# VMEConnectors.net
KiCad netlist of a schematic drawn in Altium Designer
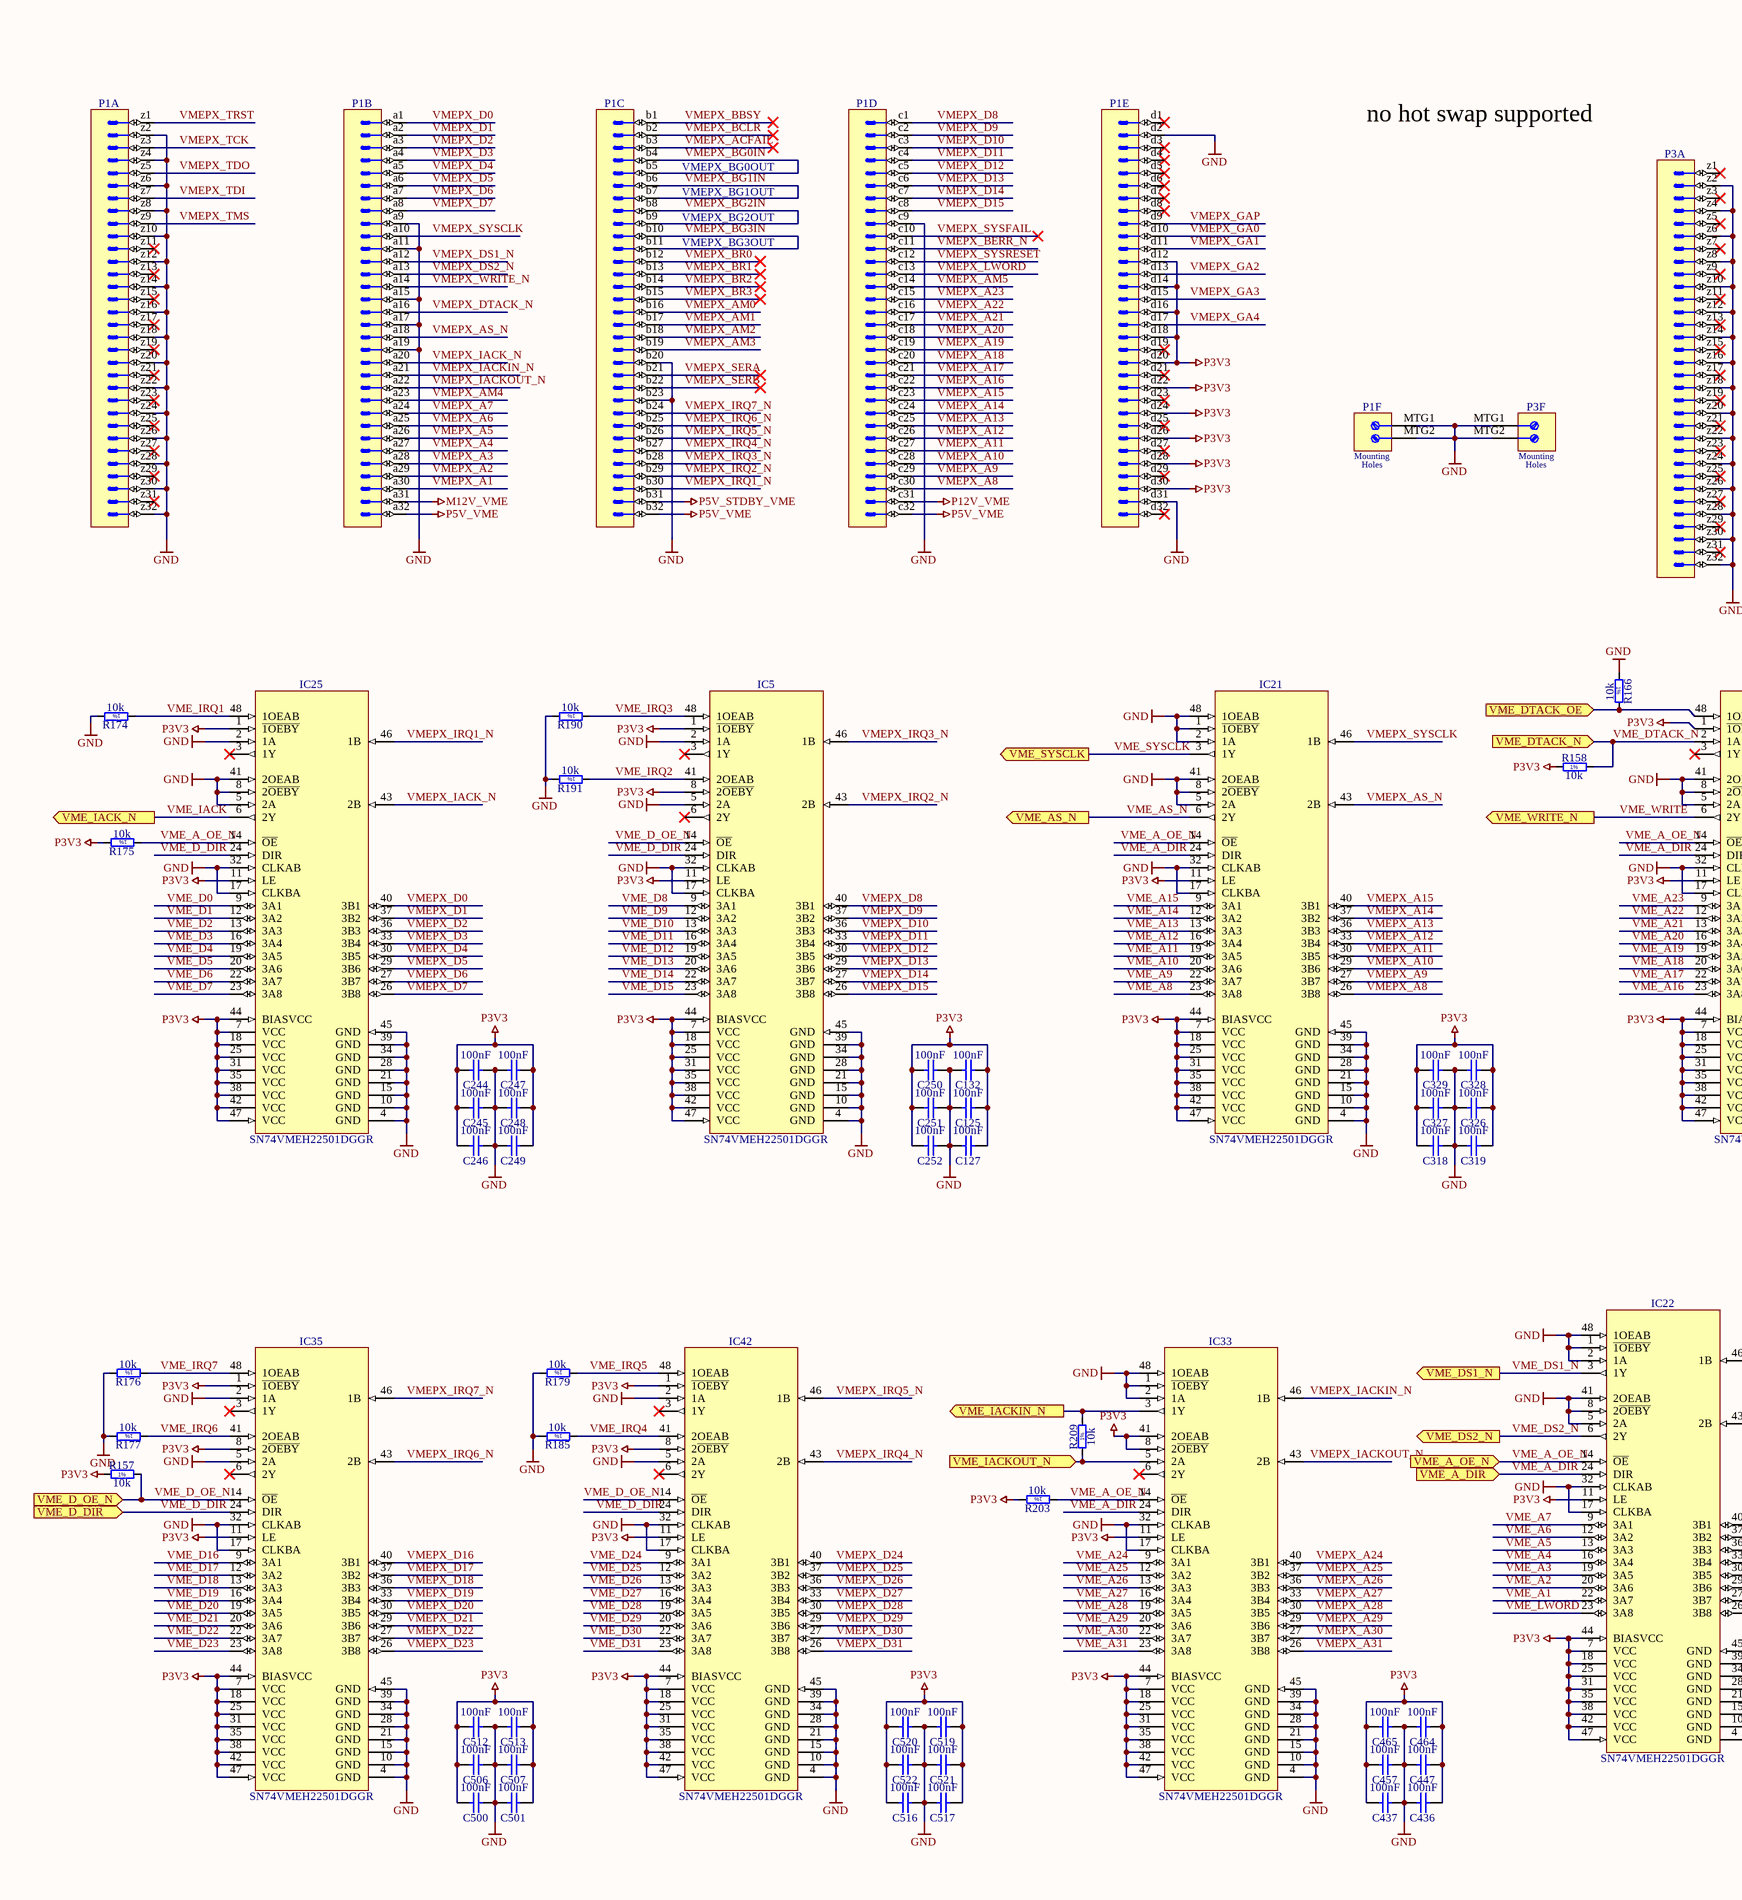
[diagram p0: VMEConnectors.SchDoc, left]
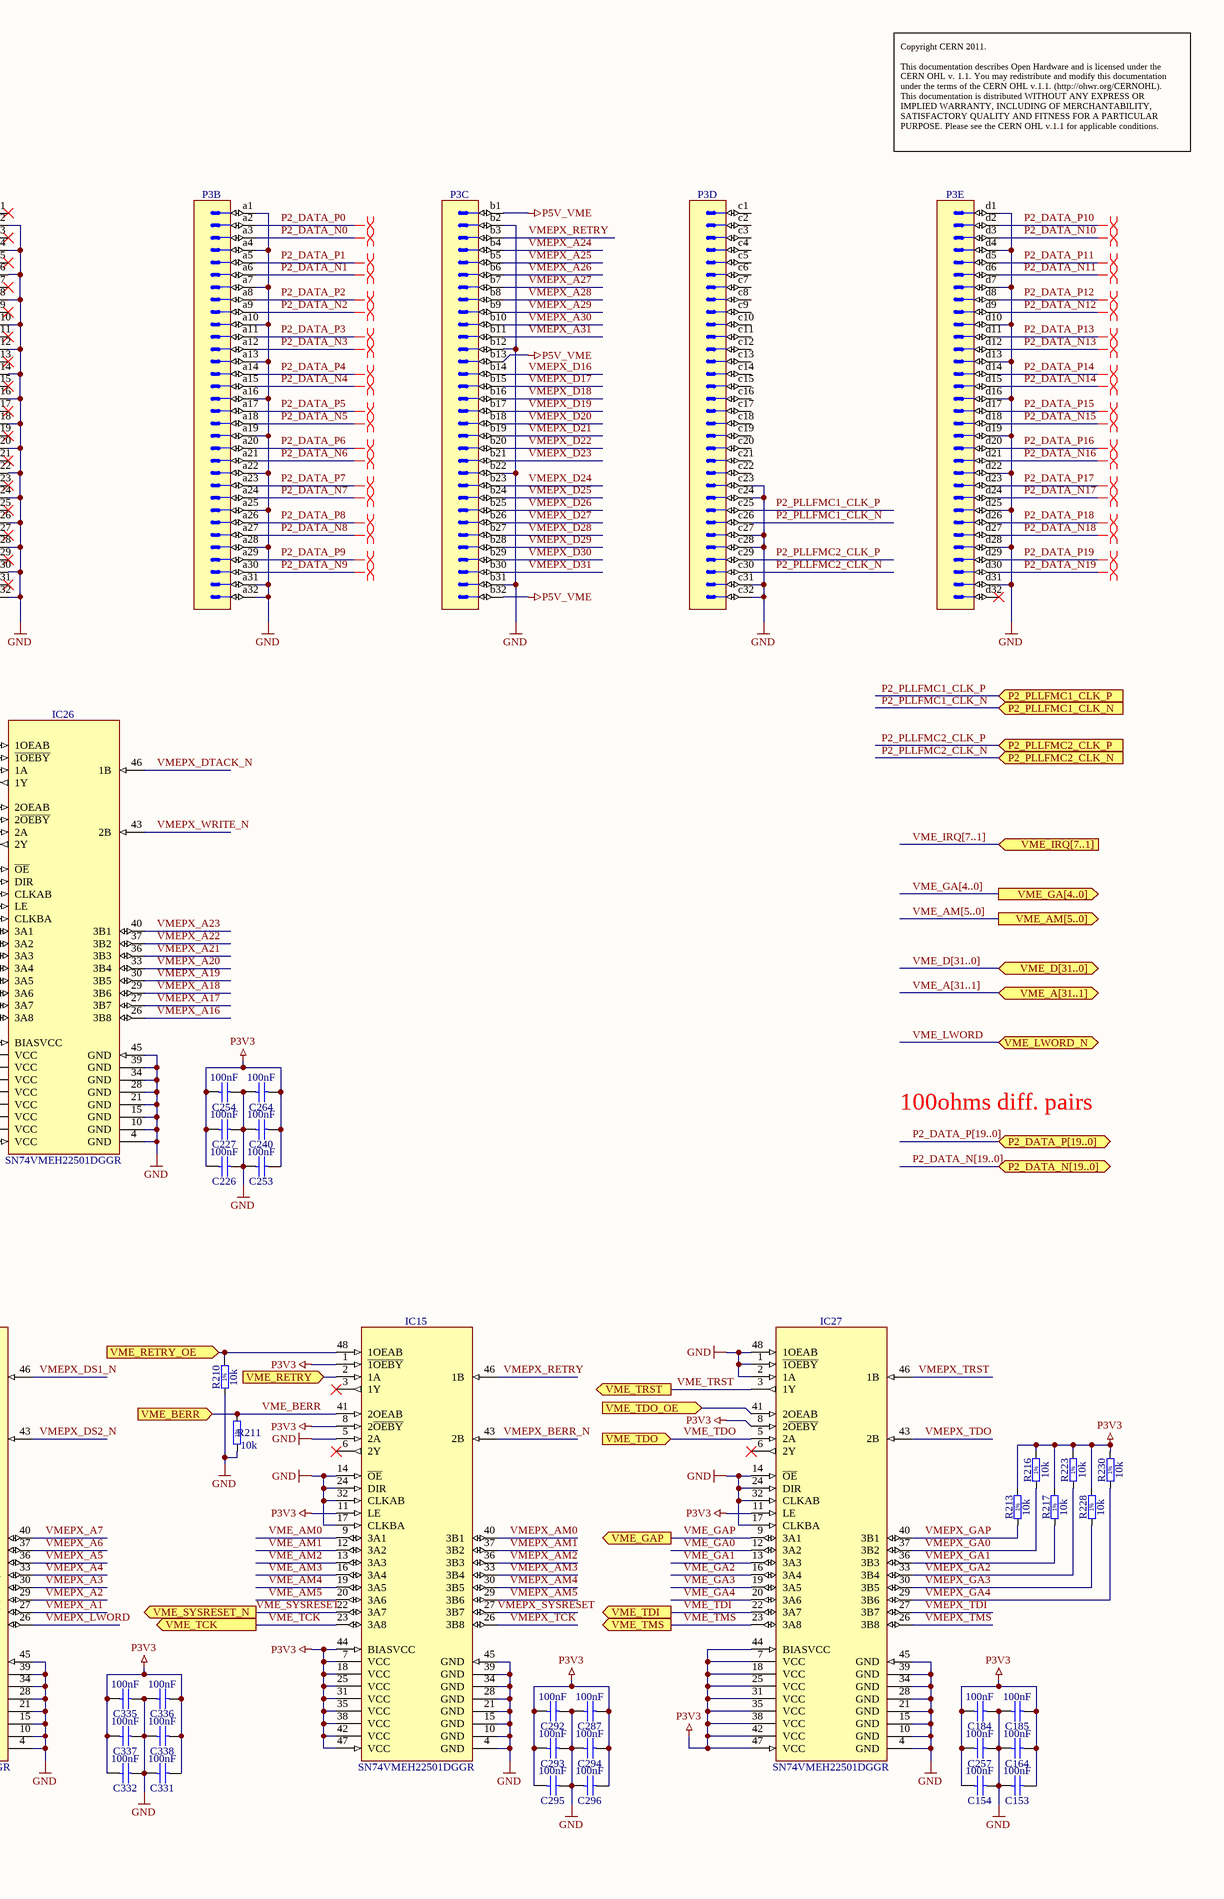
[diagram p1: VMEConnectors.SchDoc, right]

(export (version "E")
  (design (tool "Eeschema 10.0.6"))
  (components
    (comp (ref "C125")
      (value "100nF")
      (footprint "CAPC1005X55N")
      (description "Non-polarised capacitor")
      (fields
        (field (name "PART NUMBER") "CC0402_100NF_16V_10%_X7R")
        (field (name "VOLTAGE") "16V")
        (field (name "AUTHOR") "CERN DEM JLC")
      )
      (libsource (lib "Capacitors") (part "Capacitor - non polarized"))
    )
    (comp (ref "C127")
      (value "100nF")
      (footprint "CAPC1005X55N")
      (description "Non-polarised capacitor")
      (fields
        (field (name "PART NUMBER") "CC0402_100NF_16V_10%_X7R")
        (field (name "VOLTAGE") "16V")
        (field (name "AUTHOR") "CERN DEM JLC")
      )
      (libsource (lib "Capacitors") (part "Capacitor - non polarized"))
    )
    (comp (ref "C132")
      (value "100nF")
      (footprint "CAPC1005X55N")
      (description "Non-polarised capacitor")
      (fields
        (field (name "PART NUMBER") "CC0402_100NF_16V_10%_X7R")
        (field (name "VOLTAGE") "16V")
        (field (name "AUTHOR") "CERN DEM JLC")
      )
      (libsource (lib "Capacitors") (part "Capacitor - non polarized"))
    )
    (comp (ref "C153")
      (value "100nF")
      (footprint "CAPC1005X55N")
      (description "Non-polarised capacitor")
      (fields
        (field (name "PART NUMBER") "CC0402_100NF_16V_10%_X7R")
        (field (name "VOLTAGE") "16V")
        (field (name "AUTHOR") "CERN DEM JLC")
      )
      (libsource (lib "Capacitors") (part "Capacitor - non polarized"))
    )
    (comp (ref "C154")
      (value "100nF")
      (footprint "CAPC1005X55N")
      (description "Non-polarised capacitor")
      (fields
        (field (name "PART NUMBER") "CC0402_100NF_16V_10%_X7R")
        (field (name "VOLTAGE") "16V")
        (field (name "AUTHOR") "CERN DEM JLC")
      )
      (libsource (lib "Capacitors") (part "Capacitor - non polarized"))
    )
    (comp (ref "C164")
      (value "100nF")
      (footprint "CAPC1005X55N")
      (description "Non-polarised capacitor")
      (fields
        (field (name "PART NUMBER") "CC0402_100NF_16V_10%_X7R")
        (field (name "VOLTAGE") "16V")
        (field (name "AUTHOR") "CERN DEM JLC")
      )
      (libsource (lib "Capacitors") (part "Capacitor - non polarized"))
    )
    (comp (ref "C184")
      (value "100nF")
      (footprint "CAPC1005X55N")
      (description "Non-polarised capacitor")
      (fields
        (field (name "PART NUMBER") "CC0402_100NF_16V_10%_X7R")
        (field (name "VOLTAGE") "16V")
        (field (name "AUTHOR") "CERN DEM JLC")
      )
      (libsource (lib "Capacitors") (part "Capacitor - non polarized"))
    )
    (comp (ref "C185")
      (value "100nF")
      (footprint "CAPC1005X55N")
      (description "Non-polarised capacitor")
      (fields
        (field (name "PART NUMBER") "CC0402_100NF_16V_10%_X7R")
        (field (name "VOLTAGE") "16V")
        (field (name "AUTHOR") "CERN DEM JLC")
      )
      (libsource (lib "Capacitors") (part "Capacitor - non polarized"))
    )
    (comp (ref "C226")
      (value "100nF")
      (footprint "CAPC1005X55N")
      (description "Non-polarised capacitor")
      (fields
        (field (name "PART NUMBER") "CC0402_100NF_16V_10%_X7R")
        (field (name "VOLTAGE") "16V")
        (field (name "AUTHOR") "CERN DEM JLC")
      )
      (libsource (lib "Capacitors") (part "Capacitor - non polarized"))
    )
    (comp (ref "C227")
      (value "100nF")
      (footprint "CAPC1005X55N")
      (description "Non-polarised capacitor")
      (fields
        (field (name "PART NUMBER") "CC0402_100NF_16V_10%_X7R")
        (field (name "VOLTAGE") "16V")
        (field (name "AUTHOR") "CERN DEM JLC")
      )
      (libsource (lib "Capacitors") (part "Capacitor - non polarized"))
    )
    (comp (ref "C240")
      (value "100nF")
      (footprint "CAPC1005X55N")
      (description "Non-polarised capacitor")
      (fields
        (field (name "PART NUMBER") "CC0402_100NF_16V_10%_X7R")
        (field (name "VOLTAGE") "16V")
        (field (name "AUTHOR") "CERN DEM JLC")
      )
      (libsource (lib "Capacitors") (part "Capacitor - non polarized"))
    )
    (comp (ref "C244")
      (value "100nF")
      (footprint "CAPC1005X55N")
      (description "Non-polarised capacitor")
      (fields
        (field (name "PART NUMBER") "CC0402_100NF_16V_10%_X7R")
        (field (name "VOLTAGE") "16V")
        (field (name "AUTHOR") "CERN DEM JLC")
      )
      (libsource (lib "Capacitors") (part "Capacitor - non polarized"))
    )
    (comp (ref "C245")
      (value "100nF")
      (footprint "CAPC1005X55N")
      (description "Non-polarised capacitor")
      (fields
        (field (name "PART NUMBER") "CC0402_100NF_16V_10%_X7R")
        (field (name "VOLTAGE") "16V")
        (field (name "AUTHOR") "CERN DEM JLC")
      )
      (libsource (lib "Capacitors") (part "Capacitor - non polarized"))
    )
    (comp (ref "C246")
      (value "100nF")
      (footprint "CAPC1005X55N")
      (description "Non-polarised capacitor")
      (fields
        (field (name "PART NUMBER") "CC0402_100NF_16V_10%_X7R")
        (field (name "VOLTAGE") "16V")
        (field (name "AUTHOR") "CERN DEM JLC")
      )
      (libsource (lib "Capacitors") (part "Capacitor - non polarized"))
    )
    (comp (ref "C247")
      (value "100nF")
      (footprint "CAPC1005X55N")
      (description "Non-polarised capacitor")
      (fields
        (field (name "PART NUMBER") "CC0402_100NF_16V_10%_X7R")
        (field (name "VOLTAGE") "16V")
        (field (name "AUTHOR") "CERN DEM JLC")
      )
      (libsource (lib "Capacitors") (part "Capacitor - non polarized"))
    )
    (comp (ref "C248")
      (value "100nF")
      (footprint "CAPC1005X55N")
      (description "Non-polarised capacitor")
      (fields
        (field (name "PART NUMBER") "CC0402_100NF_16V_10%_X7R")
        (field (name "VOLTAGE") "16V")
        (field (name "AUTHOR") "CERN DEM JLC")
      )
      (libsource (lib "Capacitors") (part "Capacitor - non polarized"))
    )
    (comp (ref "C249")
      (value "100nF")
      (footprint "CAPC1005X55N")
      (description "Non-polarised capacitor")
      (fields
        (field (name "PART NUMBER") "CC0402_100NF_16V_10%_X7R")
        (field (name "VOLTAGE") "16V")
        (field (name "AUTHOR") "CERN DEM JLC")
      )
      (libsource (lib "Capacitors") (part "Capacitor - non polarized"))
    )
    (comp (ref "C250")
      (value "100nF")
      (footprint "CAPC1005X55N")
      (description "Non-polarised capacitor")
      (fields
        (field (name "PART NUMBER") "CC0402_100NF_16V_10%_X7R")
        (field (name "VOLTAGE") "16V")
        (field (name "AUTHOR") "CERN DEM JLC")
      )
      (libsource (lib "Capacitors") (part "Capacitor - non polarized"))
    )
    (comp (ref "C251")
      (value "100nF")
      (footprint "CAPC1005X55N")
      (description "Non-polarised capacitor")
      (fields
        (field (name "PART NUMBER") "CC0402_100NF_16V_10%_X7R")
        (field (name "VOLTAGE") "16V")
        (field (name "AUTHOR") "CERN DEM JLC")
      )
      (libsource (lib "Capacitors") (part "Capacitor - non polarized"))
    )
    (comp (ref "C252")
      (value "100nF")
      (footprint "CAPC1005X55N")
      (description "Non-polarised capacitor")
      (fields
        (field (name "PART NUMBER") "CC0402_100NF_16V_10%_X7R")
        (field (name "VOLTAGE") "16V")
        (field (name "AUTHOR") "CERN DEM JLC")
      )
      (libsource (lib "Capacitors") (part "Capacitor - non polarized"))
    )
    (comp (ref "C253")
      (value "100nF")
      (footprint "CAPC1005X55N")
      (description "Non-polarised capacitor")
      (fields
        (field (name "PART NUMBER") "CC0402_100NF_16V_10%_X7R")
        (field (name "VOLTAGE") "16V")
        (field (name "AUTHOR") "CERN DEM JLC")
      )
      (libsource (lib "Capacitors") (part "Capacitor - non polarized"))
    )
    (comp (ref "C254")
      (value "100nF")
      (footprint "CAPC1005X55N")
      (description "Non-polarised capacitor")
      (fields
        (field (name "PART NUMBER") "CC0402_100NF_16V_10%_X7R")
        (field (name "VOLTAGE") "16V")
        (field (name "AUTHOR") "CERN DEM JLC")
      )
      (libsource (lib "Capacitors") (part "Capacitor - non polarized"))
    )
    (comp (ref "C257")
      (value "100nF")
      (footprint "CAPC1005X55N")
      (description "Non-polarised capacitor")
      (fields
        (field (name "PART NUMBER") "CC0402_100NF_16V_10%_X7R")
        (field (name "VOLTAGE") "16V")
        (field (name "AUTHOR") "CERN DEM JLC")
      )
      (libsource (lib "Capacitors") (part "Capacitor - non polarized"))
    )
    (comp (ref "C264")
      (value "100nF")
      (footprint "CAPC1005X55N")
      (description "Non-polarised capacitor")
      (fields
        (field (name "PART NUMBER") "CC0402_100NF_16V_10%_X7R")
        (field (name "VOLTAGE") "16V")
        (field (name "AUTHOR") "CERN DEM JLC")
      )
      (libsource (lib "Capacitors") (part "Capacitor - non polarized"))
    )
    (comp (ref "C287")
      (value "100nF")
      (footprint "CAPC1005X55N")
      (description "Non-polarised capacitor")
      (fields
        (field (name "PART NUMBER") "CC0402_100NF_16V_10%_X7R")
        (field (name "VOLTAGE") "16V")
        (field (name "AUTHOR") "CERN DEM JLC")
      )
      (libsource (lib "Capacitors") (part "Capacitor - non polarized"))
    )
    (comp (ref "C292")
      (value "100nF")
      (footprint "CAPC1005X55N")
      (description "Non-polarised capacitor")
      (fields
        (field (name "PART NUMBER") "CC0402_100NF_16V_10%_X7R")
        (field (name "VOLTAGE") "16V")
        (field (name "AUTHOR") "CERN DEM JLC")
      )
      (libsource (lib "Capacitors") (part "Capacitor - non polarized"))
    )
    (comp (ref "C293")
      (value "100nF")
      (footprint "CAPC1005X55N")
      (description "Non-polarised capacitor")
      (fields
        (field (name "PART NUMBER") "CC0402_100NF_16V_10%_X7R")
        (field (name "VOLTAGE") "16V")
        (field (name "AUTHOR") "CERN DEM JLC")
      )
      (libsource (lib "Capacitors") (part "Capacitor - non polarized"))
    )
    (comp (ref "C294")
      (value "100nF")
      (footprint "CAPC1005X55N")
      (description "Non-polarised capacitor")
      (fields
        (field (name "PART NUMBER") "CC0402_100NF_16V_10%_X7R")
        (field (name "VOLTAGE") "16V")
        (field (name "AUTHOR") "CERN DEM JLC")
      )
      (libsource (lib "Capacitors") (part "Capacitor - non polarized"))
    )
    (comp (ref "C295")
      (value "100nF")
      (footprint "CAPC1005X55N")
      (description "Non-polarised capacitor")
      (fields
        (field (name "PART NUMBER") "CC0402_100NF_16V_10%_X7R")
        (field (name "VOLTAGE") "16V")
        (field (name "AUTHOR") "CERN DEM JLC")
      )
      (libsource (lib "Capacitors") (part "Capacitor - non polarized"))
    )
    (comp (ref "C296")
      (value "100nF")
      (footprint "CAPC1005X55N")
      (description "Non-polarised capacitor")
      (fields
        (field (name "PART NUMBER") "CC0402_100NF_16V_10%_X7R")
        (field (name "VOLTAGE") "16V")
        (field (name "AUTHOR") "CERN DEM JLC")
      )
      (libsource (lib "Capacitors") (part "Capacitor - non polarized"))
    )
    (comp (ref "C318")
      (value "100nF")
      (footprint "CAPC1005X55N")
      (description "Non-polarised capacitor")
      (fields
        (field (name "PART NUMBER") "CC0402_100NF_16V_10%_X7R")
        (field (name "VOLTAGE") "16V")
        (field (name "AUTHOR") "CERN DEM JLC")
      )
      (libsource (lib "Capacitors") (part "Capacitor - non polarized"))
    )
    (comp (ref "C319")
      (value "100nF")
      (footprint "CAPC1005X55N")
      (description "Non-polarised capacitor")
      (fields
        (field (name "PART NUMBER") "CC0402_100NF_16V_10%_X7R")
        (field (name "VOLTAGE") "16V")
        (field (name "AUTHOR") "CERN DEM JLC")
      )
      (libsource (lib "Capacitors") (part "Capacitor - non polarized"))
    )
    (comp (ref "C326")
      (value "100nF")
      (footprint "CAPC1005X55N")
      (description "Non-polarised capacitor")
      (fields
        (field (name "PART NUMBER") "CC0402_100NF_16V_10%_X7R")
        (field (name "VOLTAGE") "16V")
        (field (name "AUTHOR") "CERN DEM JLC")
      )
      (libsource (lib "Capacitors") (part "Capacitor - non polarized"))
    )
    (comp (ref "C327")
      (value "100nF")
      (footprint "CAPC1005X55N")
      (description "Non-polarised capacitor")
      (fields
        (field (name "PART NUMBER") "CC0402_100NF_16V_10%_X7R")
        (field (name "VOLTAGE") "16V")
        (field (name "AUTHOR") "CERN DEM JLC")
      )
      (libsource (lib "Capacitors") (part "Capacitor - non polarized"))
    )
    (comp (ref "C328")
      (value "100nF")
      (footprint "CAPC1005X55N")
      (description "Non-polarised capacitor")
      (fields
        (field (name "PART NUMBER") "CC0402_100NF_16V_10%_X7R")
        (field (name "VOLTAGE") "16V")
        (field (name "AUTHOR") "CERN DEM JLC")
      )
      (libsource (lib "Capacitors") (part "Capacitor - non polarized"))
    )
    (comp (ref "C329")
      (value "100nF")
      (footprint "CAPC1005X55N")
      (description "Non-polarised capacitor")
      (fields
        (field (name "PART NUMBER") "CC0402_100NF_16V_10%_X7R")
        (field (name "VOLTAGE") "16V")
        (field (name "AUTHOR") "CERN DEM JLC")
      )
      (libsource (lib "Capacitors") (part "Capacitor - non polarized"))
    )
    (comp (ref "C331")
      (value "100nF")
      (footprint "CAPC1005X55N")
      (description "Non-polarised capacitor")
      (fields
        (field (name "PART NUMBER") "CC0402_100NF_16V_10%_X7R")
        (field (name "VOLTAGE") "16V")
        (field (name "AUTHOR") "CERN DEM JLC")
      )
      (libsource (lib "Capacitors") (part "Capacitor - non polarized"))
    )
    (comp (ref "C332")
      (value "100nF")
      (footprint "CAPC1005X55N")
      (description "Non-polarised capacitor")
      (fields
        (field (name "PART NUMBER") "CC0402_100NF_16V_10%_X7R")
        (field (name "VOLTAGE") "16V")
        (field (name "AUTHOR") "CERN DEM JLC")
      )
      (libsource (lib "Capacitors") (part "Capacitor - non polarized"))
    )
    (comp (ref "C335")
      (value "100nF")
      (footprint "CAPC1005X55N")
      (description "Non-polarised capacitor")
      (fields
        (field (name "PART NUMBER") "CC0402_100NF_16V_10%_X7R")
        (field (name "VOLTAGE") "16V")
        (field (name "AUTHOR") "CERN DEM JLC")
      )
      (libsource (lib "Capacitors") (part "Capacitor - non polarized"))
    )
    (comp (ref "C336")
      (value "100nF")
      (footprint "CAPC1005X55N")
      (description "Non-polarised capacitor")
      (fields
        (field (name "PART NUMBER") "CC0402_100NF_16V_10%_X7R")
        (field (name "VOLTAGE") "16V")
        (field (name "AUTHOR") "CERN DEM JLC")
      )
      (libsource (lib "Capacitors") (part "Capacitor - non polarized"))
    )
    (comp (ref "C337")
      (value "100nF")
      (footprint "CAPC1005X55N")
      (description "Non-polarised capacitor")
      (fields
        (field (name "PART NUMBER") "CC0402_100NF_16V_10%_X7R")
        (field (name "VOLTAGE") "16V")
        (field (name "AUTHOR") "CERN DEM JLC")
      )
      (libsource (lib "Capacitors") (part "Capacitor - non polarized"))
    )
    (comp (ref "C338")
      (value "100nF")
      (footprint "CAPC1005X55N")
      (description "Non-polarised capacitor")
      (fields
        (field (name "PART NUMBER") "CC0402_100NF_16V_10%_X7R")
        (field (name "VOLTAGE") "16V")
        (field (name "AUTHOR") "CERN DEM JLC")
      )
      (libsource (lib "Capacitors") (part "Capacitor - non polarized"))
    )
    (comp (ref "C436")
      (value "100nF")
      (footprint "CAPC1005X55N")
      (description "Non-polarised capacitor")
      (fields
        (field (name "PART NUMBER") "CC0402_100NF_16V_10%_X7R")
        (field (name "VOLTAGE") "16V")
        (field (name "AUTHOR") "CERN DEM JLC")
      )
      (libsource (lib "Capacitors") (part "Capacitor - non polarized"))
    )
    (comp (ref "C437")
      (value "100nF")
      (footprint "CAPC1005X55N")
      (description "Non-polarised capacitor")
      (fields
        (field (name "PART NUMBER") "CC0402_100NF_16V_10%_X7R")
        (field (name "VOLTAGE") "16V")
        (field (name "AUTHOR") "CERN DEM JLC")
      )
      (libsource (lib "Capacitors") (part "Capacitor - non polarized"))
    )
    (comp (ref "C447")
      (value "100nF")
      (footprint "CAPC1005X55N")
      (description "Non-polarised capacitor")
      (fields
        (field (name "PART NUMBER") "CC0402_100NF_16V_10%_X7R")
        (field (name "VOLTAGE") "16V")
        (field (name "AUTHOR") "CERN DEM JLC")
      )
      (libsource (lib "Capacitors") (part "Capacitor - non polarized"))
    )
    (comp (ref "C457")
      (value "100nF")
      (footprint "CAPC1005X55N")
      (description "Non-polarised capacitor")
      (fields
        (field (name "PART NUMBER") "CC0402_100NF_16V_10%_X7R")
        (field (name "VOLTAGE") "16V")
        (field (name "AUTHOR") "CERN DEM JLC")
      )
      (libsource (lib "Capacitors") (part "Capacitor - non polarized"))
    )
    (comp (ref "C464")
      (value "100nF")
      (footprint "CAPC1005X55N")
      (description "Non-polarised capacitor")
      (fields
        (field (name "PART NUMBER") "CC0402_100NF_16V_10%_X7R")
        (field (name "VOLTAGE") "16V")
        (field (name "AUTHOR") "CERN DEM JLC")
      )
      (libsource (lib "Capacitors") (part "Capacitor - non polarized"))
    )
    (comp (ref "C465")
      (value "100nF")
      (footprint "CAPC1005X55N")
      (description "Non-polarised capacitor")
      (fields
        (field (name "PART NUMBER") "CC0402_100NF_16V_10%_X7R")
        (field (name "VOLTAGE") "16V")
        (field (name "AUTHOR") "CERN DEM JLC")
      )
      (libsource (lib "Capacitors") (part "Capacitor - non polarized"))
    )
    (comp (ref "C500")
      (value "100nF")
      (footprint "CAPC1005X55N")
      (description "Non-polarised capacitor")
      (fields
        (field (name "PART NUMBER") "CC0402_100NF_16V_10%_X7R")
        (field (name "VOLTAGE") "16V")
        (field (name "AUTHOR") "CERN DEM JLC")
      )
      (libsource (lib "Capacitors") (part "Capacitor - non polarized"))
    )
    (comp (ref "C501")
      (value "100nF")
      (footprint "CAPC1005X55N")
      (description "Non-polarised capacitor")
      (fields
        (field (name "PART NUMBER") "CC0402_100NF_16V_10%_X7R")
        (field (name "VOLTAGE") "16V")
        (field (name "AUTHOR") "CERN DEM JLC")
      )
      (libsource (lib "Capacitors") (part "Capacitor - non polarized"))
    )
    (comp (ref "C506")
      (value "100nF")
      (footprint "CAPC1005X55N")
      (description "Non-polarised capacitor")
      (fields
        (field (name "PART NUMBER") "CC0402_100NF_16V_10%_X7R")
        (field (name "VOLTAGE") "16V")
        (field (name "AUTHOR") "CERN DEM JLC")
      )
      (libsource (lib "Capacitors") (part "Capacitor - non polarized"))
    )
    (comp (ref "C507")
      (value "100nF")
      (footprint "CAPC1005X55N")
      (description "Non-polarised capacitor")
      (fields
        (field (name "PART NUMBER") "CC0402_100NF_16V_10%_X7R")
        (field (name "VOLTAGE") "16V")
        (field (name "AUTHOR") "CERN DEM JLC")
      )
      (libsource (lib "Capacitors") (part "Capacitor - non polarized"))
    )
    (comp (ref "C512")
      (value "100nF")
      (footprint "CAPC1005X55N")
      (description "Non-polarised capacitor")
      (fields
        (field (name "PART NUMBER") "CC0402_100NF_16V_10%_X7R")
        (field (name "VOLTAGE") "16V")
        (field (name "AUTHOR") "CERN DEM JLC")
      )
      (libsource (lib "Capacitors") (part "Capacitor - non polarized"))
    )
    (comp (ref "C513")
      (value "100nF")
      (footprint "CAPC1005X55N")
      (description "Non-polarised capacitor")
      (fields
        (field (name "PART NUMBER") "CC0402_100NF_16V_10%_X7R")
        (field (name "VOLTAGE") "16V")
        (field (name "AUTHOR") "CERN DEM JLC")
      )
      (libsource (lib "Capacitors") (part "Capacitor - non polarized"))
    )
    (comp (ref "C516")
      (value "100nF")
      (footprint "CAPC1005X55N")
      (description "Non-polarised capacitor")
      (fields
        (field (name "PART NUMBER") "CC0402_100NF_16V_10%_X7R")
        (field (name "VOLTAGE") "16V")
        (field (name "AUTHOR") "CERN DEM JLC")
      )
      (libsource (lib "Capacitors") (part "Capacitor - non polarized"))
    )
    (comp (ref "C517")
      (value "100nF")
      (footprint "CAPC1005X55N")
      (description "Non-polarised capacitor")
      (fields
        (field (name "PART NUMBER") "CC0402_100NF_16V_10%_X7R")
        (field (name "VOLTAGE") "16V")
        (field (name "AUTHOR") "CERN DEM JLC")
      )
      (libsource (lib "Capacitors") (part "Capacitor - non polarized"))
    )
    (comp (ref "C519")
      (value "100nF")
      (footprint "CAPC1005X55N")
      (description "Non-polarised capacitor")
      (fields
        (field (name "PART NUMBER") "CC0402_100NF_16V_10%_X7R")
        (field (name "VOLTAGE") "16V")
        (field (name "AUTHOR") "CERN DEM JLC")
      )
      (libsource (lib "Capacitors") (part "Capacitor - non polarized"))
    )
    (comp (ref "C520")
      (value "100nF")
      (footprint "CAPC1005X55N")
      (description "Non-polarised capacitor")
      (fields
        (field (name "PART NUMBER") "CC0402_100NF_16V_10%_X7R")
        (field (name "VOLTAGE") "16V")
        (field (name "AUTHOR") "CERN DEM JLC")
      )
      (libsource (lib "Capacitors") (part "Capacitor - non polarized"))
    )
    (comp (ref "C521")
      (value "100nF")
      (footprint "CAPC1005X55N")
      (description "Non-polarised capacitor")
      (fields
        (field (name "PART NUMBER") "CC0402_100NF_16V_10%_X7R")
        (field (name "VOLTAGE") "16V")
        (field (name "AUTHOR") "CERN DEM JLC")
      )
      (libsource (lib "Capacitors") (part "Capacitor - non polarized"))
    )
    (comp (ref "C522")
      (value "100nF")
      (footprint "CAPC1005X55N")
      (description "Non-polarised capacitor")
      (fields
        (field (name "PART NUMBER") "CC0402_100NF_16V_10%_X7R")
        (field (name "VOLTAGE") "16V")
        (field (name "AUTHOR") "CERN DEM JLC")
      )
      (libsource (lib "Capacitors") (part "Capacitor - non polarized"))
    )
    (comp (ref "IC5")
      (value "SN74VMEH22501DGGR")
      (footprint "SOP50P810X120-48N")
      (description "8-Bit Universal Bus Transceiver and Two 1-Bit Bus Transceivers with 3-State Outputs")
      (fields (field (name "MANUFACTURER") "TEXAS INSTRUMENTS") (field (name "AUTHOR") "CERN DEM JLC"))
      (libsource (lib "ICs And Semiconductors") (part "74VMEH22501"))
    )
    (comp (ref "IC15")
      (value "SN74VMEH22501DGGR")
      (footprint "SOP50P810X120-48N")
      (description "8-Bit Universal Bus Transceiver and Two 1-Bit Bus Transceivers with 3-State Outputs")
      (fields (field (name "MANUFACTURER") "TEXAS INSTRUMENTS") (field (name "AUTHOR") "CERN DEM JLC"))
      (libsource (lib "ICs And Semiconductors") (part "74VMEH22501"))
    )
    (comp (ref "IC21")
      (value "SN74VMEH22501DGGR")
      (footprint "SOP50P810X120-48N")
      (description "8-Bit Universal Bus Transceiver and Two 1-Bit Bus Transceivers with 3-State Outputs")
      (fields (field (name "MANUFACTURER") "TEXAS INSTRUMENTS") (field (name "AUTHOR") "CERN DEM JLC"))
      (libsource (lib "ICs And Semiconductors") (part "74VMEH22501"))
    )
    (comp (ref "IC22")
      (value "SN74VMEH22501DGGR")
      (footprint "SOP50P810X120-48N")
      (description "8-Bit Universal Bus Transceiver and Two 1-Bit Bus Transceivers with 3-State Outputs")
      (fields (field (name "MANUFACTURER") "TEXAS INSTRUMENTS") (field (name "AUTHOR") "CERN DEM JLC"))
      (libsource (lib "ICs And Semiconductors") (part "74VMEH22501"))
    )
    (comp (ref "IC25")
      (value "SN74VMEH22501DGGR")
      (footprint "SOP50P810X120-48N")
      (description "8-Bit Universal Bus Transceiver and Two 1-Bit Bus Transceivers with 3-State Outputs")
      (fields (field (name "MANUFACTURER") "TEXAS INSTRUMENTS") (field (name "AUTHOR") "CERN DEM JLC"))
      (libsource (lib "ICs And Semiconductors") (part "74VMEH22501"))
    )
    (comp (ref "IC26")
      (value "SN74VMEH22501DGGR")
      (footprint "SOP50P810X120-48N")
      (description "8-Bit Universal Bus Transceiver and Two 1-Bit Bus Transceivers with 3-State Outputs")
      (fields (field (name "MANUFACTURER") "TEXAS INSTRUMENTS") (field (name "AUTHOR") "CERN DEM JLC"))
      (libsource (lib "ICs And Semiconductors") (part "74VMEH22501"))
    )
    (comp (ref "IC27")
      (value "SN74VMEH22501DGGR")
      (footprint "SOP50P810X120-48N")
      (description "8-Bit Universal Bus Transceiver and Two 1-Bit Bus Transceivers with 3-State Outputs")
      (fields (field (name "MANUFACTURER") "TEXAS INSTRUMENTS") (field (name "AUTHOR") "CERN DEM JLC"))
      (libsource (lib "ICs And Semiconductors") (part "74VMEH22501"))
    )
    (comp (ref "IC33")
      (value "SN74VMEH22501DGGR")
      (footprint "SOP50P810X120-48N")
      (description "8-Bit Universal Bus Transceiver and Two 1-Bit Bus Transceivers with 3-State Outputs")
      (fields (field (name "MANUFACTURER") "TEXAS INSTRUMENTS") (field (name "AUTHOR") "CERN DEM JLC"))
      (libsource (lib "ICs And Semiconductors") (part "74VMEH22501"))
    )
    (comp (ref "IC35")
      (value "SN74VMEH22501DGGR")
      (footprint "SOP50P810X120-48N")
      (description "8-Bit Universal Bus Transceiver and Two 1-Bit Bus Transceivers with 3-State Outputs")
      (fields (field (name "MANUFACTURER") "TEXAS INSTRUMENTS") (field (name "AUTHOR") "CERN DEM JLC"))
      (libsource (lib "ICs And Semiconductors") (part "74VMEH22501"))
    )
    (comp (ref "IC42")
      (value "SN74VMEH22501DGGR")
      (footprint "SOP50P810X120-48N")
      (description "8-Bit Universal Bus Transceiver and Two 1-Bit Bus Transceivers with 3-State Outputs")
      (fields (field (name "MANUFACTURER") "TEXAS INSTRUMENTS") (field (name "AUTHOR") "CERN DEM JLC"))
      (libsource (lib "ICs And Semiconductors") (part "74VMEH22501"))
    )
    (comp (ref "P1")
      (value "HAR-BUS 64")
      (footprint "HARTING_02 01 160 2101")
      (description "Connector 160zabcd Male (5x32)")
      (fields
        (field (name "PART NUMBER") "HARTING_02 01 160 2101")
        (field (name "MANUFACTURER") "HARTING")
        (field (name "AUTHOR") "CERN DEM JLC")
      )
      (libsource (lib "") (part "Connector 160zabcd Male (5x32)_2"))
    )
    (comp (ref "P3")
      (value "HAR-BUS 64")
      (footprint "HARTING_02 01 160 2101")
      (description "Connector 160zabcd Male (5x32)")
      (fields
        (field (name "PART NUMBER") "HARTING_02 01 160 2101")
        (field (name "MANUFACTURER") "HARTING")
        (field (name "AUTHOR") "CERN DEM JLC")
      )
      (libsource (lib "") (part "Connector 160zabcd Male (5x32)_1"))
    )
    (comp (ref "R157")
      (value "10k")
      (footprint "RESC1608X55N")
      (description "Resistor - 1%")
      (fields
        (field (name "PART NUMBER") "R0603_10K_1%_0.1W_100PPM")
        (field (name "POWER") "0.1W")
        (field (name "AUTHOR") "CERN DEM JLC")
      )
      (libsource (lib "Resistors") (part "Resistor - 1%"))
    )
    (comp (ref "R158")
      (value "10k")
      (footprint "RESC1608X55N")
      (description "Resistor - 1%")
      (fields
        (field (name "PART NUMBER") "R0603_10K_1%_0.1W_100PPM")
        (field (name "POWER") "0.1W")
        (field (name "AUTHOR") "CERN DEM JLC")
      )
      (libsource (lib "Resistors") (part "Resistor - 1%"))
    )
    (comp (ref "R166")
      (value "10k")
      (footprint "RESC1608X55N")
      (description "Resistor - 1%")
      (fields
        (field (name "PART NUMBER") "R0603_10K_1%_0.1W_100PPM")
        (field (name "POWER") "0.1W")
        (field (name "AUTHOR") "CERN DEM JLC")
      )
      (libsource (lib "Resistors") (part "Resistor - 1%"))
    )
    (comp (ref "R174")
      (value "10k")
      (footprint "RESC1608X55N")
      (description "Resistor - 1%")
      (fields
        (field (name "PART NUMBER") "R0603_10K_1%_0.1W_100PPM")
        (field (name "POWER") "0.1W")
        (field (name "AUTHOR") "CERN DEM JLC")
      )
      (libsource (lib "Resistors") (part "Resistor - 1%"))
    )
    (comp (ref "R175")
      (value "10k")
      (footprint "RESC1608X55N")
      (description "Resistor - 1%")
      (fields
        (field (name "PART NUMBER") "R0603_10K_1%_0.1W_100PPM")
        (field (name "POWER") "0.1W")
        (field (name "AUTHOR") "CERN DEM JLC")
      )
      (libsource (lib "Resistors") (part "Resistor - 1%"))
    )
    (comp (ref "R176")
      (value "10k")
      (footprint "RESC1608X55N")
      (description "Resistor - 1%")
      (fields
        (field (name "PART NUMBER") "R0603_10K_1%_0.1W_100PPM")
        (field (name "POWER") "0.1W")
        (field (name "AUTHOR") "CERN DEM JLC")
      )
      (libsource (lib "Resistors") (part "Resistor - 1%"))
    )
    (comp (ref "R177")
      (value "10k")
      (footprint "RESC1608X55N")
      (description "Resistor - 1%")
      (fields
        (field (name "PART NUMBER") "R0603_10K_1%_0.1W_100PPM")
        (field (name "POWER") "0.1W")
        (field (name "AUTHOR") "CERN DEM JLC")
      )
      (libsource (lib "Resistors") (part "Resistor - 1%"))
    )
    (comp (ref "R179")
      (value "10k")
      (footprint "RESC1608X55N")
      (description "Resistor - 1%")
      (fields
        (field (name "PART NUMBER") "R0603_10K_1%_0.1W_100PPM")
        (field (name "POWER") "0.1W")
        (field (name "AUTHOR") "CERN DEM JLC")
      )
      (libsource (lib "Resistors") (part "Resistor - 1%"))
    )
    (comp (ref "R185")
      (value "10k")
      (footprint "RESC1608X55N")
      (description "Resistor - 1%")
      (fields
        (field (name "PART NUMBER") "R0603_10K_1%_0.1W_100PPM")
        (field (name "POWER") "0.1W")
        (field (name "AUTHOR") "CERN DEM JLC")
      )
      (libsource (lib "Resistors") (part "Resistor - 1%"))
    )
    (comp (ref "R190")
      (value "10k")
      (footprint "RESC1608X55N")
      (description "Resistor - 1%")
      (fields
        (field (name "PART NUMBER") "R0603_10K_1%_0.1W_100PPM")
        (field (name "POWER") "0.1W")
        (field (name "AUTHOR") "CERN DEM JLC")
      )
      (libsource (lib "Resistors") (part "Resistor - 1%"))
    )
    (comp (ref "R191")
      (value "10k")
      (footprint "RESC1608X55N")
      (description "Resistor - 1%")
      (fields
        (field (name "PART NUMBER") "R0603_10K_1%_0.1W_100PPM")
        (field (name "POWER") "0.1W")
        (field (name "AUTHOR") "CERN DEM JLC")
      )
      (libsource (lib "Resistors") (part "Resistor - 1%"))
    )
    (comp (ref "R203")
      (value "10k")
      (footprint "RESC1608X55N")
      (description "Resistor - 1%")
      (fields
        (field (name "PART NUMBER") "R0603_10K_1%_0.1W_100PPM")
        (field (name "POWER") "0.1W")
        (field (name "AUTHOR") "CERN DEM JLC")
      )
      (libsource (lib "Resistors") (part "Resistor - 1%"))
    )
    (comp (ref "R209")
      (value "10k")
      (footprint "RESC1608X55N")
      (description "Resistor - 1%")
      (fields
        (field (name "PART NUMBER") "R0603_10K_1%_0.1W_100PPM")
        (field (name "POWER") "0.1W")
        (field (name "AUTHOR") "CERN DEM JLC")
      )
      (libsource (lib "Resistors") (part "Resistor - 1%"))
    )
    (comp (ref "R210")
      (value "10k")
      (footprint "RESC1608X55N")
      (description "Resistor - 1%")
      (fields
        (field (name "PART NUMBER") "R0603_10K_1%_0.1W_100PPM")
        (field (name "POWER") "0.1W")
        (field (name "AUTHOR") "CERN DEM JLC")
      )
      (libsource (lib "Resistors") (part "Resistor - 1%"))
    )
    (comp (ref "R211")
      (value "10k")
      (footprint "RESC1608X55N")
      (description "Resistor - 1%")
      (fields
        (field (name "PART NUMBER") "R0603_10K_1%_0.1W_100PPM")
        (field (name "POWER") "0.1W")
        (field (name "AUTHOR") "CERN DEM JLC")
      )
      (libsource (lib "Resistors") (part "Resistor - 1%"))
    )
    (comp (ref "R213")
      (value "10k")
      (footprint "RESC1608X55N")
      (description "Resistor - 1%")
      (fields
        (field (name "PART NUMBER") "R0603_10K_1%_0.1W_100PPM")
        (field (name "POWER") "0.1W")
        (field (name "AUTHOR") "CERN DEM JLC")
      )
      (libsource (lib "Resistors") (part "Resistor - 1%"))
    )
    (comp (ref "R216")
      (value "10k")
      (footprint "RESC1608X55N")
      (description "Resistor - 1%")
      (fields
        (field (name "PART NUMBER") "R0603_10K_1%_0.1W_100PPM")
        (field (name "POWER") "0.1W")
        (field (name "AUTHOR") "CERN DEM JLC")
      )
      (libsource (lib "Resistors") (part "Resistor - 1%"))
    )
    (comp (ref "R217")
      (value "10k")
      (footprint "RESC1608X55N")
      (description "Resistor - 1%")
      (fields
        (field (name "PART NUMBER") "R0603_10K_1%_0.1W_100PPM")
        (field (name "POWER") "0.1W")
        (field (name "AUTHOR") "CERN DEM JLC")
      )
      (libsource (lib "Resistors") (part "Resistor - 1%"))
    )
    (comp (ref "R223")
      (value "10k")
      (footprint "RESC1608X55N")
      (description "Resistor - 1%")
      (fields
        (field (name "PART NUMBER") "R0603_10K_1%_0.1W_100PPM")
        (field (name "POWER") "0.1W")
        (field (name "AUTHOR") "CERN DEM JLC")
      )
      (libsource (lib "Resistors") (part "Resistor - 1%"))
    )
    (comp (ref "R228")
      (value "10k")
      (footprint "RESC1608X55N")
      (description "Resistor - 1%")
      (fields
        (field (name "PART NUMBER") "R0603_10K_1%_0.1W_100PPM")
        (field (name "POWER") "0.1W")
        (field (name "AUTHOR") "CERN DEM JLC")
      )
      (libsource (lib "Resistors") (part "Resistor - 1%"))
    )
    (comp (ref "R230")
      (value "10k")
      (footprint "RESC1608X55N")
      (description "Resistor - 1%")
      (fields
        (field (name "PART NUMBER") "R0603_10K_1%_0.1W_100PPM")
        (field (name "POWER") "0.1W")
        (field (name "AUTHOR") "CERN DEM JLC")
      )
      (libsource (lib "Resistors") (part "Resistor - 1%"))
    )
  )
  (nets
    (net (code "1") (name "/P2_DATA_N0") (class "Default")
      (node (ref "P3") (pin "a3") (pinfunction "a3_a3") (pintype "bidirectional"))
    )
    (net (code "2") (name "/P2_DATA_N1") (class "Default")
      (node (ref "P3") (pin "a6") (pinfunction "a6_a6") (pintype "bidirectional"))
    )
    (net (code "3") (name "/P2_DATA_N2") (class "Default")
      (node (ref "P3") (pin "a9") (pinfunction "a9_a9") (pintype "bidirectional"))
    )
    (net (code "4") (name "/P2_DATA_N3") (class "Default")
      (node (ref "P3") (pin "a12") (pinfunction "a12_a12") (pintype "bidirectional"))
    )
    (net (code "5") (name "/P2_DATA_N4") (class "Default")
      (node (ref "P3") (pin "a15") (pinfunction "a15_a15") (pintype "bidirectional"))
    )
    (net (code "6") (name "/P2_DATA_N5") (class "Default")
      (node (ref "P3") (pin "a18") (pinfunction "a18_a18") (pintype "bidirectional"))
    )
    (net (code "7") (name "/P2_DATA_N6") (class "Default")
      (node (ref "P3") (pin "a21") (pinfunction "a21_a21") (pintype "bidirectional"))
    )
    (net (code "8") (name "/P2_DATA_N7") (class "Default")
      (node (ref "P3") (pin "a24") (pinfunction "a24_a24") (pintype "bidirectional"))
    )
    (net (code "9") (name "/P2_DATA_N8") (class "Default")
      (node (ref "P3") (pin "a27") (pinfunction "a27_a27") (pintype "bidirectional"))
    )
    (net (code "10") (name "/P2_DATA_N9") (class "Default")
      (node (ref "P3") (pin "a30") (pinfunction "a30_a30") (pintype "bidirectional"))
    )
    (net (code "11") (name "/P2_DATA_N10") (class "Default")
      (node (ref "P3") (pin "d3") (pinfunction "d3_d3") (pintype "bidirectional"))
    )
    (net (code "12") (name "/P2_DATA_N11") (class "Default")
      (node (ref "P3") (pin "d6") (pinfunction "d6_d6") (pintype "bidirectional"))
    )
    (net (code "13") (name "/P2_DATA_N12") (class "Default")
      (node (ref "P3") (pin "d9") (pinfunction "d9_d9") (pintype "bidirectional"))
    )
    (net (code "14") (name "/P2_DATA_N13") (class "Default")
      (node (ref "P3") (pin "d12") (pinfunction "d12_d12") (pintype "bidirectional"))
    )
    (net (code "15") (name "/P2_DATA_N14") (class "Default")
      (node (ref "P3") (pin "d15") (pinfunction "d15_d15") (pintype "bidirectional"))
    )
    (net (code "16") (name "/P2_DATA_N15") (class "Default")
      (node (ref "P3") (pin "d18") (pinfunction "d18_d18") (pintype "bidirectional"))
    )
    (net (code "17") (name "/P2_DATA_N16") (class "Default")
      (node (ref "P3") (pin "d21") (pinfunction "d21_d21") (pintype "bidirectional"))
    )
    (net (code "18") (name "/P2_DATA_N17") (class "Default")
      (node (ref "P3") (pin "d24") (pinfunction "d24_d24") (pintype "bidirectional"))
    )
    (net (code "19") (name "/P2_DATA_N18") (class "Default")
      (node (ref "P3") (pin "d27") (pinfunction "d27_d27") (pintype "bidirectional"))
    )
    (net (code "20") (name "/P2_DATA_N19") (class "Default")
      (node (ref "P3") (pin "d30") (pinfunction "d30_d30") (pintype "bidirectional"))
    )
    (net (code "22") (name "/P2_DATA_P0") (class "Default")
      (node (ref "P3") (pin "a2") (pinfunction "a2_a2") (pintype "bidirectional"))
    )
    (net (code "23") (name "/P2_DATA_P1") (class "Default")
      (node (ref "P3") (pin "a5") (pinfunction "a5_a5") (pintype "bidirectional"))
    )
    (net (code "24") (name "/P2_DATA_P2") (class "Default")
      (node (ref "P3") (pin "a8") (pinfunction "a8_a8") (pintype "bidirectional"))
    )
    (net (code "25") (name "/P2_DATA_P3") (class "Default")
      (node (ref "P3") (pin "a11") (pinfunction "a11_a11") (pintype "bidirectional"))
    )
    (net (code "26") (name "/P2_DATA_P4") (class "Default")
      (node (ref "P3") (pin "a14") (pinfunction "a14_a14") (pintype "bidirectional"))
    )
    (net (code "27") (name "/P2_DATA_P5") (class "Default")
      (node (ref "P3") (pin "a17") (pinfunction "a17_a17") (pintype "bidirectional"))
    )
    (net (code "28") (name "/P2_DATA_P6") (class "Default")
      (node (ref "P3") (pin "a20") (pinfunction "a20_a20") (pintype "bidirectional"))
    )
    (net (code "29") (name "/P2_DATA_P7") (class "Default")
      (node (ref "P3") (pin "a23") (pinfunction "a23_a23") (pintype "bidirectional"))
    )
    (net (code "30") (name "/P2_DATA_P8") (class "Default")
      (node (ref "P3") (pin "a26") (pinfunction "a26_a26") (pintype "bidirectional"))
    )
    (net (code "31") (name "/P2_DATA_P9") (class "Default")
      (node (ref "P3") (pin "a29") (pinfunction "a29_a29") (pintype "bidirectional"))
    )
    (net (code "32") (name "/P2_DATA_P10") (class "Default")
      (node (ref "P3") (pin "d2") (pinfunction "d2_d2") (pintype "bidirectional"))
    )
    (net (code "33") (name "/P2_DATA_P11") (class "Default")
      (node (ref "P3") (pin "d5") (pinfunction "d5_d5") (pintype "bidirectional"))
    )
    (net (code "34") (name "/P2_DATA_P12") (class "Default")
      (node (ref "P3") (pin "d8") (pinfunction "d8_d8") (pintype "bidirectional"))
    )
    (net (code "35") (name "/P2_DATA_P13") (class "Default")
      (node (ref "P3") (pin "d11") (pinfunction "d11_d11") (pintype "bidirectional"))
    )
    (net (code "36") (name "/P2_DATA_P14") (class "Default")
      (node (ref "P3") (pin "d14") (pinfunction "d14_d14") (pintype "bidirectional"))
    )
    (net (code "37") (name "/P2_DATA_P15") (class "Default")
      (node (ref "P3") (pin "d17") (pinfunction "d17_d17") (pintype "bidirectional"))
    )
    (net (code "38") (name "/P2_DATA_P16") (class "Default")
      (node (ref "P3") (pin "d20") (pinfunction "d20_d20") (pintype "bidirectional"))
    )
    (net (code "39") (name "/P2_DATA_P17") (class "Default")
      (node (ref "P3") (pin "d23") (pinfunction "d23_d23") (pintype "bidirectional"))
    )
    (net (code "40") (name "/P2_DATA_P18") (class "Default")
      (node (ref "P3") (pin "d26") (pinfunction "d26_d26") (pintype "bidirectional"))
    )
    (net (code "41") (name "/P2_DATA_P19") (class "Default")
      (node (ref "P3") (pin "d29") (pinfunction "d29_d29") (pintype "bidirectional"))
    )
    (net (code "43") (name "/P2_PLLFMC1_CLK_N") (class "Default")
      (node (ref "P3") (pin "c26") (pinfunction "c26_c26") (pintype "bidirectional"))
    )
    (net (code "44") (name "/P2_PLLFMC1_CLK_P") (class "Default")
      (node (ref "P3") (pin "c25") (pinfunction "c25_c25") (pintype "bidirectional"))
    )
    (net (code "45") (name "/P2_PLLFMC2_CLK_N") (class "Default")
      (node (ref "P3") (pin "c30") (pinfunction "c30_c30") (pintype "bidirectional"))
    )
    (net (code "46") (name "/P2_PLLFMC2_CLK_P") (class "Default")
      (node (ref "P3") (pin "c29") (pinfunction "c29_c29") (pintype "bidirectional"))
    )
    (net (code "47") (name "/VMEPX_A1") (class "Default")
      (node (ref "IC22") (pin "27") (pinfunction "3B7_27") (pintype "bidirectional"))
      (node (ref "P1") (pin "a30") (pinfunction "a30_a30") (pintype "bidirectional"))
    )
    (net (code "48") (name "/VMEPX_A2") (class "Default")
      (node (ref "IC22") (pin "29") (pinfunction "3B6_29") (pintype "bidirectional"))
      (node (ref "P1") (pin "a29") (pinfunction "a29_a29") (pintype "bidirectional"))
    )
    (net (code "49") (name "/VMEPX_A3") (class "Default")
      (node (ref "IC22") (pin "30") (pinfunction "3B5_30") (pintype "bidirectional"))
      (node (ref "P1") (pin "a28") (pinfunction "a28_a28") (pintype "bidirectional"))
    )
    (net (code "50") (name "/VMEPX_A4") (class "Default")
      (node (ref "IC22") (pin "33") (pinfunction "3B4_33") (pintype "bidirectional"))
      (node (ref "P1") (pin "a27") (pinfunction "a27_a27") (pintype "bidirectional"))
    )
    (net (code "51") (name "/VMEPX_A5") (class "Default")
      (node (ref "IC22") (pin "36") (pinfunction "3B3_36") (pintype "bidirectional"))
      (node (ref "P1") (pin "a26") (pinfunction "a26_a26") (pintype "bidirectional"))
    )
    (net (code "52") (name "/VMEPX_A6") (class "Default")
      (node (ref "IC22") (pin "37") (pinfunction "3B2_37") (pintype "bidirectional"))
      (node (ref "P1") (pin "a25") (pinfunction "a25_a25") (pintype "bidirectional"))
    )
    (net (code "53") (name "/VMEPX_A7") (class "Default")
      (node (ref "IC22") (pin "40") (pinfunction "3B1_40") (pintype "bidirectional"))
      (node (ref "P1") (pin "a24") (pinfunction "a24_a24") (pintype "bidirectional"))
    )
    (net (code "54") (name "/VMEPX_A8") (class "Default")
      (node (ref "IC21") (pin "26") (pinfunction "3B8_26") (pintype "bidirectional"))
      (node (ref "P1") (pin "c30") (pinfunction "c30_c30") (pintype "bidirectional"))
    )
    (net (code "55") (name "/VMEPX_A9") (class "Default")
      (node (ref "IC21") (pin "27") (pinfunction "3B7_27") (pintype "bidirectional"))
      (node (ref "P1") (pin "c29") (pinfunction "c29_c29") (pintype "bidirectional"))
    )
    (net (code "56") (name "/VMEPX_A10") (class "Default")
      (node (ref "IC21") (pin "29") (pinfunction "3B6_29") (pintype "bidirectional"))
      (node (ref "P1") (pin "c28") (pinfunction "c28_c28") (pintype "bidirectional"))
    )
    (net (code "57") (name "/VMEPX_A11") (class "Default")
      (node (ref "IC21") (pin "30") (pinfunction "3B5_30") (pintype "bidirectional"))
      (node (ref "P1") (pin "c27") (pinfunction "c27_c27") (pintype "bidirectional"))
    )
    (net (code "58") (name "/VMEPX_A12") (class "Default")
      (node (ref "IC21") (pin "33") (pinfunction "3B4_33") (pintype "bidirectional"))
      (node (ref "P1") (pin "c26") (pinfunction "c26_c26") (pintype "bidirectional"))
    )
    (net (code "59") (name "/VMEPX_A13") (class "Default")
      (node (ref "IC21") (pin "36") (pinfunction "3B3_36") (pintype "bidirectional"))
      (node (ref "P1") (pin "c25") (pinfunction "c25_c25") (pintype "bidirectional"))
    )
    (net (code "60") (name "/VMEPX_A14") (class "Default")
      (node (ref "IC21") (pin "37") (pinfunction "3B2_37") (pintype "bidirectional"))
      (node (ref "P1") (pin "c24") (pinfunction "c24_c24") (pintype "bidirectional"))
    )
    (net (code "61") (name "/VMEPX_A15") (class "Default")
      (node (ref "IC21") (pin "40") (pinfunction "3B1_40") (pintype "bidirectional"))
      (node (ref "P1") (pin "c23") (pinfunction "c23_c23") (pintype "bidirectional"))
    )
    (net (code "62") (name "/VMEPX_A16") (class "Default")
      (node (ref "IC26") (pin "26") (pinfunction "3B8_26") (pintype "bidirectional"))
      (node (ref "P1") (pin "c22") (pinfunction "c22_c22") (pintype "bidirectional"))
    )
    (net (code "63") (name "/VMEPX_A17") (class "Default")
      (node (ref "IC26") (pin "27") (pinfunction "3B7_27") (pintype "bidirectional"))
      (node (ref "P1") (pin "c21") (pinfunction "c21_c21") (pintype "bidirectional"))
    )
    (net (code "64") (name "/VMEPX_A18") (class "Default")
      (node (ref "IC26") (pin "29") (pinfunction "3B6_29") (pintype "bidirectional"))
      (node (ref "P1") (pin "c20") (pinfunction "c20_c20") (pintype "bidirectional"))
    )
    (net (code "65") (name "/VMEPX_A19") (class "Default")
      (node (ref "IC26") (pin "30") (pinfunction "3B5_30") (pintype "bidirectional"))
      (node (ref "P1") (pin "c19") (pinfunction "c19_c19") (pintype "bidirectional"))
    )
    (net (code "66") (name "/VMEPX_A20") (class "Default")
      (node (ref "IC26") (pin "33") (pinfunction "3B4_33") (pintype "bidirectional"))
      (node (ref "P1") (pin "c18") (pinfunction "c18_c18") (pintype "bidirectional"))
    )
    (net (code "67") (name "/VMEPX_A21") (class "Default")
      (node (ref "IC26") (pin "36") (pinfunction "3B3_36") (pintype "bidirectional"))
      (node (ref "P1") (pin "c17") (pinfunction "c17_c17") (pintype "bidirectional"))
    )
    (net (code "68") (name "/VMEPX_A22") (class "Default")
      (node (ref "IC26") (pin "37") (pinfunction "3B2_37") (pintype "bidirectional"))
      (node (ref "P1") (pin "c16") (pinfunction "c16_c16") (pintype "bidirectional"))
    )
    (net (code "69") (name "/VMEPX_A23") (class "Default")
      (node (ref "IC26") (pin "40") (pinfunction "3B1_40") (pintype "bidirectional"))
      (node (ref "P1") (pin "c15") (pinfunction "c15_c15") (pintype "bidirectional"))
    )
    (net (code "70") (name "/VMEPX_A24") (class "Default")
      (node (ref "IC33") (pin "40") (pinfunction "3B1_40") (pintype "bidirectional"))
      (node (ref "P3") (pin "b4") (pinfunction "b4_b4") (pintype "bidirectional"))
    )
    (net (code "71") (name "/VMEPX_A25") (class "Default")
      (node (ref "IC33") (pin "37") (pinfunction "3B2_37") (pintype "bidirectional"))
      (node (ref "P3") (pin "b5") (pinfunction "b5_b5") (pintype "bidirectional"))
    )
    (net (code "72") (name "/VMEPX_A26") (class "Default")
      (node (ref "IC33") (pin "36") (pinfunction "3B3_36") (pintype "bidirectional"))
      (node (ref "P3") (pin "b6") (pinfunction "b6_b6") (pintype "bidirectional"))
    )
    (net (code "73") (name "/VMEPX_A27") (class "Default")
      (node (ref "IC33") (pin "33") (pinfunction "3B4_33") (pintype "bidirectional"))
      (node (ref "P3") (pin "b7") (pinfunction "b7_b7") (pintype "bidirectional"))
    )
    (net (code "74") (name "/VMEPX_A28") (class "Default")
      (node (ref "IC33") (pin "30") (pinfunction "3B5_30") (pintype "bidirectional"))
      (node (ref "P3") (pin "b8") (pinfunction "b8_b8") (pintype "bidirectional"))
    )
    (net (code "75") (name "/VMEPX_A29") (class "Default")
      (node (ref "IC33") (pin "29") (pinfunction "3B6_29") (pintype "bidirectional"))
      (node (ref "P3") (pin "b9") (pinfunction "b9_b9") (pintype "bidirectional"))
    )
    (net (code "76") (name "/VMEPX_A30") (class "Default")
      (node (ref "IC33") (pin "27") (pinfunction "3B7_27") (pintype "bidirectional"))
      (node (ref "P3") (pin "b10") (pinfunction "b10_b10") (pintype "bidirectional"))
    )
    (net (code "77") (name "/VMEPX_A31") (class "Default")
      (node (ref "IC33") (pin "26") (pinfunction "3B8_26") (pintype "bidirectional"))
      (node (ref "P3") (pin "b11") (pinfunction "b11_b11") (pintype "bidirectional"))
    )
    (net (code "78") (name "/VMEPX_ACFAIL") (class "Default")
      (node (ref "P1") (pin "b3") (pinfunction "b3_b3") (pintype "bidirectional+no_connect"))
    )
    (net (code "79") (name "/VMEPX_AM0") (class "Default")
      (node (ref "IC15") (pin "40") (pinfunction "3B1_40") (pintype "bidirectional"))
      (node (ref "P1") (pin "b16") (pinfunction "b16_b16") (pintype "bidirectional"))
    )
    (net (code "80") (name "/VMEPX_AM1") (class "Default")
      (node (ref "IC15") (pin "37") (pinfunction "3B2_37") (pintype "bidirectional"))
      (node (ref "P1") (pin "b17") (pinfunction "b17_b17") (pintype "bidirectional"))
    )
    (net (code "81") (name "/VMEPX_AM2") (class "Default")
      (node (ref "IC15") (pin "36") (pinfunction "3B3_36") (pintype "bidirectional"))
      (node (ref "P1") (pin "b18") (pinfunction "b18_b18") (pintype "bidirectional"))
    )
    (net (code "82") (name "/VMEPX_AM3") (class "Default")
      (node (ref "IC15") (pin "33") (pinfunction "3B4_33") (pintype "bidirectional"))
      (node (ref "P1") (pin "b19") (pinfunction "b19_b19") (pintype "bidirectional"))
    )
    (net (code "83") (name "/VMEPX_AM4") (class "Default")
      (node (ref "IC15") (pin "30") (pinfunction "3B5_30") (pintype "bidirectional"))
      (node (ref "P1") (pin "a23") (pinfunction "a23_a23") (pintype "bidirectional"))
    )
    (net (code "84") (name "/VMEPX_AM5") (class "Default")
      (node (ref "IC15") (pin "29") (pinfunction "3B6_29") (pintype "bidirectional"))
      (node (ref "P1") (pin "c14") (pinfunction "c14_c14") (pintype "bidirectional"))
    )
    (net (code "85") (name "/VMEPX_AS_N") (class "Default")
      (node (ref "IC21") (pin "43") (pinfunction "2B_43") (pintype "input"))
      (node (ref "P1") (pin "a18") (pinfunction "a18_a18") (pintype "bidirectional"))
    )
    (net (code "86") (name "/VMEPX_BBSY") (class "Default")
      (node (ref "P1") (pin "b1") (pinfunction "b1_b1") (pintype "bidirectional+no_connect"))
    )
    (net (code "87") (name "/VMEPX_BCLR") (class "Default")
      (node (ref "P1") (pin "b2") (pinfunction "b2_b2") (pintype "bidirectional+no_connect"))
    )
    (net (code "88") (name "/VMEPX_BERR_N") (class "Default")
      (node (ref "IC15") (pin "43") (pinfunction "2B_43") (pintype "input"))
      (node (ref "P1") (pin "c11") (pinfunction "c11_c11") (pintype "bidirectional"))
    )
    (net (code "89") (name "/VMEPX_BG0IN") (class "Default")
      (node (ref "P1") (pin "b4") (pinfunction "b4_b4") (pintype "bidirectional"))
      (node (ref "P1") (pin "b5") (pinfunction "b5_b5") (pintype "bidirectional"))
    )
    (net (code "90") (name "/VMEPX_BG1IN") (class "Default")
      (node (ref "P1") (pin "b6") (pinfunction "b6_b6") (pintype "bidirectional"))
      (node (ref "P1") (pin "b7") (pinfunction "b7_b7") (pintype "bidirectional"))
    )
    (net (code "91") (name "/VMEPX_BG2IN") (class "Default")
      (node (ref "P1") (pin "b8") (pinfunction "b8_b8") (pintype "bidirectional"))
      (node (ref "P1") (pin "b9") (pinfunction "b9_b9") (pintype "bidirectional"))
    )
    (net (code "92") (name "/VMEPX_BG3IN") (class "Default")
      (node (ref "P1") (pin "b10") (pinfunction "b10_b10") (pintype "bidirectional"))
      (node (ref "P1") (pin "b11") (pinfunction "b11_b11") (pintype "bidirectional"))
    )
    (net (code "93") (name "/VMEPX_BR0") (class "Default")
      (node (ref "P1") (pin "b12") (pinfunction "b12_b12") (pintype "bidirectional+no_connect"))
    )
    (net (code "94") (name "/VMEPX_BR1") (class "Default")
      (node (ref "P1") (pin "b13") (pinfunction "b13_b13") (pintype "bidirectional+no_connect"))
    )
    (net (code "95") (name "/VMEPX_BR2") (class "Default")
      (node (ref "P1") (pin "b14") (pinfunction "b14_b14") (pintype "bidirectional+no_connect"))
    )
    (net (code "96") (name "/VMEPX_BR3") (class "Default")
      (node (ref "P1") (pin "b15") (pinfunction "b15_b15") (pintype "bidirectional+no_connect"))
    )
    (net (code "97") (name "/VMEPX_D0") (class "Default")
      (node (ref "IC25") (pin "40") (pinfunction "3B1_40") (pintype "bidirectional"))
      (node (ref "P1") (pin "a1") (pinfunction "a1_a1") (pintype "bidirectional"))
    )
    (net (code "98") (name "/VMEPX_D1") (class "Default")
      (node (ref "IC25") (pin "37") (pinfunction "3B2_37") (pintype "bidirectional"))
      (node (ref "P1") (pin "a2") (pinfunction "a2_a2") (pintype "bidirectional"))
    )
    (net (code "99") (name "/VMEPX_D2") (class "Default")
      (node (ref "IC25") (pin "36") (pinfunction "3B3_36") (pintype "bidirectional"))
      (node (ref "P1") (pin "a3") (pinfunction "a3_a3") (pintype "bidirectional"))
    )
    (net (code "100") (name "/VMEPX_D3") (class "Default")
      (node (ref "IC25") (pin "33") (pinfunction "3B4_33") (pintype "bidirectional"))
      (node (ref "P1") (pin "a4") (pinfunction "a4_a4") (pintype "bidirectional"))
    )
    (net (code "101") (name "/VMEPX_D4") (class "Default")
      (node (ref "IC25") (pin "30") (pinfunction "3B5_30") (pintype "bidirectional"))
      (node (ref "P1") (pin "a5") (pinfunction "a5_a5") (pintype "bidirectional"))
    )
    (net (code "102") (name "/VMEPX_D5") (class "Default")
      (node (ref "IC25") (pin "29") (pinfunction "3B6_29") (pintype "bidirectional"))
      (node (ref "P1") (pin "a6") (pinfunction "a6_a6") (pintype "bidirectional"))
    )
    (net (code "103") (name "/VMEPX_D6") (class "Default")
      (node (ref "IC25") (pin "27") (pinfunction "3B7_27") (pintype "bidirectional"))
      (node (ref "P1") (pin "a7") (pinfunction "a7_a7") (pintype "bidirectional"))
    )
    (net (code "104") (name "/VMEPX_D7") (class "Default")
      (node (ref "IC25") (pin "26") (pinfunction "3B8_26") (pintype "bidirectional"))
      (node (ref "P1") (pin "a8") (pinfunction "a8_a8") (pintype "bidirectional"))
    )
    (net (code "105") (name "/VMEPX_D8") (class "Default")
      (node (ref "IC5") (pin "40") (pinfunction "3B1_40") (pintype "bidirectional"))
      (node (ref "P1") (pin "c1") (pinfunction "c1_c1") (pintype "bidirectional"))
    )
    (net (code "106") (name "/VMEPX_D9") (class "Default")
      (node (ref "IC5") (pin "37") (pinfunction "3B2_37") (pintype "bidirectional"))
      (node (ref "P1") (pin "c2") (pinfunction "c2_c2") (pintype "bidirectional"))
    )
    (net (code "107") (name "/VMEPX_D10") (class "Default")
      (node (ref "IC5") (pin "36") (pinfunction "3B3_36") (pintype "bidirectional"))
      (node (ref "P1") (pin "c3") (pinfunction "c3_c3") (pintype "bidirectional"))
    )
    (net (code "108") (name "/VMEPX_D11") (class "Default")
      (node (ref "IC5") (pin "33") (pinfunction "3B4_33") (pintype "bidirectional"))
      (node (ref "P1") (pin "c4") (pinfunction "c4_c4") (pintype "bidirectional"))
    )
    (net (code "109") (name "/VMEPX_D12") (class "Default")
      (node (ref "IC5") (pin "30") (pinfunction "3B5_30") (pintype "bidirectional"))
      (node (ref "P1") (pin "c5") (pinfunction "c5_c5") (pintype "bidirectional"))
    )
    (net (code "110") (name "/VMEPX_D13") (class "Default")
      (node (ref "IC5") (pin "29") (pinfunction "3B6_29") (pintype "bidirectional"))
      (node (ref "P1") (pin "c6") (pinfunction "c6_c6") (pintype "bidirectional"))
    )
    (net (code "111") (name "/VMEPX_D14") (class "Default")
      (node (ref "IC5") (pin "27") (pinfunction "3B7_27") (pintype "bidirectional"))
      (node (ref "P1") (pin "c7") (pinfunction "c7_c7") (pintype "bidirectional"))
    )
    (net (code "112") (name "/VMEPX_D15") (class "Default")
      (node (ref "IC5") (pin "26") (pinfunction "3B8_26") (pintype "bidirectional"))
      (node (ref "P1") (pin "c8") (pinfunction "c8_c8") (pintype "bidirectional"))
    )
    (net (code "113") (name "/VMEPX_D16") (class "Default")
      (node (ref "IC35") (pin "40") (pinfunction "3B1_40") (pintype "bidirectional"))
      (node (ref "P3") (pin "b14") (pinfunction "b14_b14") (pintype "bidirectional"))
    )
    (net (code "114") (name "/VMEPX_D17") (class "Default")
      (node (ref "IC35") (pin "37") (pinfunction "3B2_37") (pintype "bidirectional"))
      (node (ref "P3") (pin "b15") (pinfunction "b15_b15") (pintype "bidirectional"))
    )
    (net (code "115") (name "/VMEPX_D18") (class "Default")
      (node (ref "IC35") (pin "36") (pinfunction "3B3_36") (pintype "bidirectional"))
      (node (ref "P3") (pin "b16") (pinfunction "b16_b16") (pintype "bidirectional"))
    )
    (net (code "116") (name "/VMEPX_D19") (class "Default")
      (node (ref "IC35") (pin "33") (pinfunction "3B4_33") (pintype "bidirectional"))
      (node (ref "P3") (pin "b17") (pinfunction "b17_b17") (pintype "bidirectional"))
    )
    (net (code "117") (name "/VMEPX_D20") (class "Default")
      (node (ref "IC35") (pin "30") (pinfunction "3B5_30") (pintype "bidirectional"))
      (node (ref "P3") (pin "b18") (pinfunction "b18_b18") (pintype "bidirectional"))
    )
    (net (code "118") (name "/VMEPX_D21") (class "Default")
      (node (ref "IC35") (pin "29") (pinfunction "3B6_29") (pintype "bidirectional"))
      (node (ref "P3") (pin "b19") (pinfunction "b19_b19") (pintype "bidirectional"))
    )
    (net (code "119") (name "/VMEPX_D22") (class "Default")
      (node (ref "IC35") (pin "27") (pinfunction "3B7_27") (pintype "bidirectional"))
      (node (ref "P3") (pin "b20") (pinfunction "b20_b20") (pintype "bidirectional"))
    )
    (net (code "120") (name "/VMEPX_D23") (class "Default")
      (node (ref "IC35") (pin "26") (pinfunction "3B8_26") (pintype "bidirectional"))
      (node (ref "P3") (pin "b21") (pinfunction "b21_b21") (pintype "bidirectional"))
    )
    (net (code "121") (name "/VMEPX_D24") (class "Default")
      (node (ref "IC42") (pin "40") (pinfunction "3B1_40") (pintype "bidirectional"))
      (node (ref "P3") (pin "b23") (pinfunction "b23_b23") (pintype "bidirectional"))
    )
    (net (code "122") (name "/VMEPX_D25") (class "Default")
      (node (ref "IC42") (pin "37") (pinfunction "3B2_37") (pintype "bidirectional"))
      (node (ref "P3") (pin "b24") (pinfunction "b24_b24") (pintype "bidirectional"))
    )
    (net (code "123") (name "/VMEPX_D26") (class "Default")
      (node (ref "IC42") (pin "36") (pinfunction "3B3_36") (pintype "bidirectional"))
      (node (ref "P3") (pin "b25") (pinfunction "b25_b25") (pintype "bidirectional"))
    )
    (net (code "124") (name "/VMEPX_D27") (class "Default")
      (node (ref "IC42") (pin "33") (pinfunction "3B4_33") (pintype "bidirectional"))
      (node (ref "P3") (pin "b26") (pinfunction "b26_b26") (pintype "bidirectional"))
    )
    (net (code "125") (name "/VMEPX_D28") (class "Default")
      (node (ref "IC42") (pin "30") (pinfunction "3B5_30") (pintype "bidirectional"))
      (node (ref "P3") (pin "b27") (pinfunction "b27_b27") (pintype "bidirectional"))
    )
    (net (code "126") (name "/VMEPX_D29") (class "Default")
      (node (ref "IC42") (pin "29") (pinfunction "3B6_29") (pintype "bidirectional"))
      (node (ref "P3") (pin "b28") (pinfunction "b28_b28") (pintype "bidirectional"))
    )
    (net (code "127") (name "/VMEPX_D30") (class "Default")
      (node (ref "IC42") (pin "27") (pinfunction "3B7_27") (pintype "bidirectional"))
      (node (ref "P3") (pin "b29") (pinfunction "b29_b29") (pintype "bidirectional"))
    )
    (net (code "128") (name "/VMEPX_D31") (class "Default")
      (node (ref "IC42") (pin "26") (pinfunction "3B8_26") (pintype "bidirectional"))
      (node (ref "P3") (pin "b30") (pinfunction "b30_b30") (pintype "bidirectional"))
    )
    (net (code "129") (name "/VMEPX_DS1_N") (class "Default")
      (node (ref "IC22") (pin "46") (pinfunction "1B_46") (pintype "input"))
      (node (ref "P1") (pin "a12") (pinfunction "a12_a12") (pintype "bidirectional"))
    )
    (net (code "130") (name "/VMEPX_DS2_N") (class "Default")
      (node (ref "IC22") (pin "43") (pinfunction "2B_43") (pintype "input"))
      (node (ref "P1") (pin "a13") (pinfunction "a13_a13") (pintype "bidirectional"))
    )
    (net (code "131") (name "/VMEPX_DTACK_N") (class "Default")
      (node (ref "IC26") (pin "46") (pinfunction "1B_46") (pintype "input"))
      (node (ref "P1") (pin "a16") (pinfunction "a16_a16") (pintype "bidirectional"))
    )
    (net (code "132") (name "/VMEPX_GA0") (class "Default")
      (node (ref "IC27") (pin "37") (pinfunction "3B2_37") (pintype "bidirectional"))
      (node (ref "P1") (pin "d10") (pinfunction "d10_d10") (pintype "bidirectional"))
      (node (ref "R216") (pin "1") (pinfunction "1_1") (pintype "passive"))
    )
    (net (code "133") (name "/VMEPX_GA1") (class "Default")
      (node (ref "IC27") (pin "36") (pinfunction "3B3_36") (pintype "bidirectional"))
      (node (ref "P1") (pin "d11") (pinfunction "d11_d11") (pintype "bidirectional"))
      (node (ref "R217") (pin "1") (pinfunction "1_1") (pintype "passive"))
    )
    (net (code "134") (name "/VMEPX_GA2") (class "Default")
      (node (ref "IC27") (pin "33") (pinfunction "3B4_33") (pintype "bidirectional"))
      (node (ref "P1") (pin "d13") (pinfunction "d13_d13") (pintype "bidirectional"))
      (node (ref "R223") (pin "1") (pinfunction "1_1") (pintype "passive"))
    )
    (net (code "135") (name "/VMEPX_GA3") (class "Default")
      (node (ref "IC27") (pin "30") (pinfunction "3B5_30") (pintype "bidirectional"))
      (node (ref "P1") (pin "d15") (pinfunction "d15_d15") (pintype "bidirectional"))
      (node (ref "R228") (pin "1") (pinfunction "1_1") (pintype "passive"))
    )
    (net (code "136") (name "/VMEPX_GA4") (class "Default")
      (node (ref "IC27") (pin "29") (pinfunction "3B6_29") (pintype "bidirectional"))
      (node (ref "P1") (pin "d17") (pinfunction "d17_d17") (pintype "bidirectional"))
      (node (ref "R230") (pin "1") (pinfunction "1_1") (pintype "passive"))
    )
    (net (code "137") (name "/VMEPX_GAP") (class "Default")
      (node (ref "IC27") (pin "40") (pinfunction "3B1_40") (pintype "bidirectional"))
      (node (ref "P1") (pin "d9") (pinfunction "d9_d9") (pintype "bidirectional"))
      (node (ref "R213") (pin "1") (pinfunction "1_1") (pintype "passive"))
    )
    (net (code "138") (name "/VMEPX_IACKIN_N") (class "Default")
      (node (ref "IC33") (pin "46") (pinfunction "1B_46") (pintype "input"))
      (node (ref "P1") (pin "a21") (pinfunction "a21_a21") (pintype "bidirectional"))
    )
    (net (code "139") (name "/VMEPX_IACKOUT_N") (class "Default")
      (node (ref "IC33") (pin "43") (pinfunction "2B_43") (pintype "input"))
      (node (ref "P1") (pin "a22") (pinfunction "a22_a22") (pintype "bidirectional"))
    )
    (net (code "140") (name "/VMEPX_IACK_N") (class "Default")
      (node (ref "IC25") (pin "43") (pinfunction "2B_43") (pintype "input"))
      (node (ref "P1") (pin "a20") (pinfunction "a20_a20") (pintype "bidirectional"))
    )
    (net (code "141") (name "/VMEPX_IRQ1_N") (class "Default")
      (node (ref "IC25") (pin "46") (pinfunction "1B_46") (pintype "input"))
      (node (ref "P1") (pin "b30") (pinfunction "b30_b30") (pintype "bidirectional"))
    )
    (net (code "142") (name "/VMEPX_IRQ2_N") (class "Default")
      (node (ref "IC5") (pin "43") (pinfunction "2B_43") (pintype "input"))
      (node (ref "P1") (pin "b29") (pinfunction "b29_b29") (pintype "bidirectional"))
    )
    (net (code "143") (name "/VMEPX_IRQ3_N") (class "Default")
      (node (ref "IC5") (pin "46") (pinfunction "1B_46") (pintype "input"))
      (node (ref "P1") (pin "b28") (pinfunction "b28_b28") (pintype "bidirectional"))
    )
    (net (code "144") (name "/VMEPX_IRQ4_N") (class "Default")
      (node (ref "IC42") (pin "43") (pinfunction "2B_43") (pintype "input"))
      (node (ref "P1") (pin "b27") (pinfunction "b27_b27") (pintype "bidirectional"))
    )
    (net (code "145") (name "/VMEPX_IRQ5_N") (class "Default")
      (node (ref "IC42") (pin "46") (pinfunction "1B_46") (pintype "input"))
      (node (ref "P1") (pin "b26") (pinfunction "b26_b26") (pintype "bidirectional"))
    )
    (net (code "146") (name "/VMEPX_IRQ6_N") (class "Default")
      (node (ref "IC35") (pin "43") (pinfunction "2B_43") (pintype "input"))
      (node (ref "P1") (pin "b25") (pinfunction "b25_b25") (pintype "bidirectional"))
    )
    (net (code "147") (name "/VMEPX_IRQ7_N") (class "Default")
      (node (ref "IC35") (pin "46") (pinfunction "1B_46") (pintype "input"))
      (node (ref "P1") (pin "b24") (pinfunction "b24_b24") (pintype "bidirectional"))
    )
    (net (code "148") (name "/VMEPX_LWORD") (class "Default")
      (node (ref "IC22") (pin "26") (pinfunction "3B8_26") (pintype "bidirectional"))
      (node (ref "P1") (pin "c13") (pinfunction "c13_c13") (pintype "bidirectional"))
    )
    (net (code "149") (name "/VMEPX_RETRY") (class "Default")
      (node (ref "IC15") (pin "46") (pinfunction "1B_46") (pintype "input"))
      (node (ref "P3") (pin "b3") (pinfunction "b3_b3") (pintype "bidirectional"))
    )
    (net (code "150") (name "/VMEPX_SERA") (class "Default")
      (node (ref "P1") (pin "b21") (pinfunction "b21_b21") (pintype "bidirectional+no_connect"))
    )
    (net (code "151") (name "/VMEPX_SERB") (class "Default")
      (node (ref "P1") (pin "b22") (pinfunction "b22_b22") (pintype "bidirectional+no_connect"))
    )
    (net (code "152") (name "/VMEPX_SYSCLK") (class "Default")
      (node (ref "IC21") (pin "46") (pinfunction "1B_46") (pintype "input"))
      (node (ref "P1") (pin "a10") (pinfunction "a10_a10") (pintype "bidirectional"))
    )
    (net (code "153") (name "/VMEPX_SYSFAIL") (class "Default")
      (node (ref "P1") (pin "c10") (pinfunction "c10_c10") (pintype "bidirectional+no_connect"))
    )
    (net (code "154") (name "/VMEPX_SYSRESET") (class "Default")
      (node (ref "IC15") (pin "27") (pinfunction "3B7_27") (pintype "bidirectional"))
      (node (ref "P1") (pin "c12") (pinfunction "c12_c12") (pintype "bidirectional"))
    )
    (net (code "155") (name "/VMEPX_TCK") (class "Default")
      (node (ref "IC15") (pin "26") (pinfunction "3B8_26") (pintype "bidirectional"))
      (node (ref "P1") (pin "z3") (pinfunction "z3_z3") (pintype "bidirectional"))
    )
    (net (code "156") (name "/VMEPX_TDI") (class "Default")
      (node (ref "IC27") (pin "27") (pinfunction "3B7_27") (pintype "bidirectional"))
      (node (ref "P1") (pin "z7") (pinfunction "z7_z7") (pintype "bidirectional"))
    )
    (net (code "157") (name "/VMEPX_TDO") (class "Default")
      (node (ref "IC27") (pin "43") (pinfunction "2B_43") (pintype "input"))
      (node (ref "P1") (pin "z5") (pinfunction "z5_z5") (pintype "bidirectional"))
    )
    (net (code "158") (name "/VMEPX_TMS") (class "Default")
      (node (ref "IC27") (pin "26") (pinfunction "3B8_26") (pintype "bidirectional"))
      (node (ref "P1") (pin "z9") (pinfunction "z9_z9") (pintype "bidirectional"))
    )
    (net (code "159") (name "/VMEPX_TRST") (class "Default")
      (node (ref "IC27") (pin "46") (pinfunction "1B_46") (pintype "input"))
      (node (ref "P1") (pin "z1") (pinfunction "z1_z1") (pintype "bidirectional"))
    )
    (net (code "160") (name "/VMEPX_WRITE_N") (class "Default")
      (node (ref "IC26") (pin "43") (pinfunction "2B_43") (pintype "input"))
      (node (ref "P1") (pin "a14") (pinfunction "a14_a14") (pintype "bidirectional"))
    )
    (net (code "161") (name "/VME_A1") (class "Default")
      (node (ref "IC22") (pin "22") (pinfunction "3A7_22") (pintype "bidirectional"))
    )
    (net (code "162") (name "/VME_A2") (class "Default")
      (node (ref "IC22") (pin "20") (pinfunction "3A6_20") (pintype "bidirectional"))
    )
    (net (code "163") (name "/VME_A3") (class "Default")
      (node (ref "IC22") (pin "19") (pinfunction "3A5_19") (pintype "bidirectional"))
    )
    (net (code "164") (name "/VME_A4") (class "Default")
      (node (ref "IC22") (pin "16") (pinfunction "3A4_16") (pintype "bidirectional"))
    )
    (net (code "165") (name "/VME_A5") (class "Default")
      (node (ref "IC22") (pin "13") (pinfunction "3A3_13") (pintype "bidirectional"))
    )
    (net (code "166") (name "/VME_A6") (class "Default")
      (node (ref "IC22") (pin "12") (pinfunction "3A2_12") (pintype "bidirectional"))
    )
    (net (code "167") (name "/VME_A7") (class "Default")
      (node (ref "IC22") (pin "9") (pinfunction "3A1_9") (pintype "bidirectional"))
    )
    (net (code "168") (name "/VME_A8") (class "Default")
      (node (ref "IC21") (pin "23") (pinfunction "3A8_23") (pintype "bidirectional"))
    )
    (net (code "169") (name "/VME_A9") (class "Default")
      (node (ref "IC21") (pin "22") (pinfunction "3A7_22") (pintype "bidirectional"))
    )
    (net (code "170") (name "/VME_A10") (class "Default")
      (node (ref "IC21") (pin "20") (pinfunction "3A6_20") (pintype "bidirectional"))
    )
    (net (code "171") (name "/VME_A11") (class "Default")
      (node (ref "IC21") (pin "19") (pinfunction "3A5_19") (pintype "bidirectional"))
    )
    (net (code "172") (name "/VME_A12") (class "Default")
      (node (ref "IC21") (pin "16") (pinfunction "3A4_16") (pintype "bidirectional"))
    )
    (net (code "173") (name "/VME_A13") (class "Default")
      (node (ref "IC21") (pin "13") (pinfunction "3A3_13") (pintype "bidirectional"))
    )
    (net (code "174") (name "/VME_A14") (class "Default")
      (node (ref "IC21") (pin "12") (pinfunction "3A2_12") (pintype "bidirectional"))
    )
    (net (code "175") (name "/VME_A15") (class "Default")
      (node (ref "IC21") (pin "9") (pinfunction "3A1_9") (pintype "bidirectional"))
    )
    (net (code "176") (name "/VME_A16") (class "Default")
      (node (ref "IC26") (pin "23") (pinfunction "3A8_23") (pintype "bidirectional"))
    )
    (net (code "177") (name "/VME_A17") (class "Default")
      (node (ref "IC26") (pin "22") (pinfunction "3A7_22") (pintype "bidirectional"))
    )
    (net (code "178") (name "/VME_A18") (class "Default")
      (node (ref "IC26") (pin "20") (pinfunction "3A6_20") (pintype "bidirectional"))
    )
    (net (code "179") (name "/VME_A19") (class "Default")
      (node (ref "IC26") (pin "19") (pinfunction "3A5_19") (pintype "bidirectional"))
    )
    (net (code "180") (name "/VME_A20") (class "Default")
      (node (ref "IC26") (pin "16") (pinfunction "3A4_16") (pintype "bidirectional"))
    )
    (net (code "181") (name "/VME_A21") (class "Default")
      (node (ref "IC26") (pin "13") (pinfunction "3A3_13") (pintype "bidirectional"))
    )
    (net (code "182") (name "/VME_A22") (class "Default")
      (node (ref "IC26") (pin "12") (pinfunction "3A2_12") (pintype "bidirectional"))
    )
    (net (code "183") (name "/VME_A23") (class "Default")
      (node (ref "IC26") (pin "9") (pinfunction "3A1_9") (pintype "bidirectional"))
    )
    (net (code "184") (name "/VME_A24") (class "Default")
      (node (ref "IC33") (pin "9") (pinfunction "3A1_9") (pintype "bidirectional"))
    )
    (net (code "185") (name "/VME_A25") (class "Default")
      (node (ref "IC33") (pin "12") (pinfunction "3A2_12") (pintype "bidirectional"))
    )
    (net (code "186") (name "/VME_A26") (class "Default")
      (node (ref "IC33") (pin "13") (pinfunction "3A3_13") (pintype "bidirectional"))
    )
    (net (code "187") (name "/VME_A27") (class "Default")
      (node (ref "IC33") (pin "16") (pinfunction "3A4_16") (pintype "bidirectional"))
    )
    (net (code "188") (name "/VME_A28") (class "Default")
      (node (ref "IC33") (pin "19") (pinfunction "3A5_19") (pintype "bidirectional"))
    )
    (net (code "189") (name "/VME_A29") (class "Default")
      (node (ref "IC33") (pin "20") (pinfunction "3A6_20") (pintype "bidirectional"))
    )
    (net (code "190") (name "/VME_A30") (class "Default")
      (node (ref "IC33") (pin "22") (pinfunction "3A7_22") (pintype "bidirectional"))
    )
    (net (code "191") (name "/VME_A31") (class "Default")
      (node (ref "IC33") (pin "23") (pinfunction "3A8_23") (pintype "bidirectional"))
    )
    (net (code "192") (name "/VME_AM0") (class "Default")
      (node (ref "IC15") (pin "9") (pinfunction "3A1_9") (pintype "bidirectional"))
    )
    (net (code "193") (name "/VME_AM1") (class "Default")
      (node (ref "IC15") (pin "12") (pinfunction "3A2_12") (pintype "bidirectional"))
    )
    (net (code "194") (name "/VME_AM2") (class "Default")
      (node (ref "IC15") (pin "13") (pinfunction "3A3_13") (pintype "bidirectional"))
    )
    (net (code "195") (name "/VME_AM3") (class "Default")
      (node (ref "IC15") (pin "16") (pinfunction "3A4_16") (pintype "bidirectional"))
    )
    (net (code "196") (name "/VME_AM4") (class "Default")
      (node (ref "IC15") (pin "19") (pinfunction "3A5_19") (pintype "bidirectional"))
    )
    (net (code "197") (name "/VME_AM5") (class "Default")
      (node (ref "IC15") (pin "20") (pinfunction "3A6_20") (pintype "bidirectional"))
    )
    (net (code "199") (name "/VME_AS_N") (class "Default")
      (node (ref "IC21") (pin "6") (pinfunction "2Y_6") (pintype "output"))
    )
    (net (code "201") (name "/VME_A_DIR") (class "Default")
      (node (ref "IC21") (pin "24") (pinfunction "DIR_24") (pintype "input"))
      (node (ref "IC22") (pin "24") (pinfunction "DIR_24") (pintype "input"))
      (node (ref "IC26") (pin "24") (pinfunction "DIR_24") (pintype "input"))
      (node (ref "IC33") (pin "24") (pinfunction "DIR_24") (pintype "input"))
    )
    (net (code "202") (name "/VME_A_OE_N") (class "Default")
      (node (ref "IC21") (pin "14") (pinfunction "~{OE}_14") (pintype "input"))
      (node (ref "IC22") (pin "14") (pinfunction "~{OE}_14") (pintype "input"))
      (node (ref "IC25") (pin "14") (pinfunction "~{OE}_14") (pintype "input"))
      (node (ref "IC26") (pin "14") (pinfunction "~{OE}_14") (pintype "input"))
      (node (ref "IC33") (pin "14") (pinfunction "~{OE}_14") (pintype "input"))
      (node (ref "R175") (pin "1") (pinfunction "1_1") (pintype "passive"))
      (node (ref "R203") (pin "1") (pinfunction "1_1") (pintype "passive"))
    )
    (net (code "203") (name "/VME_BERR") (class "Default")
      (node (ref "IC15") (pin "41") (pinfunction "2OEAB_41") (pintype "input"))
      (node (ref "R211") (pin "2") (pinfunction "2_2") (pintype "passive"))
    )
    (net (code "204") (name "/VME_D0") (class "Default")
      (node (ref "IC25") (pin "9") (pinfunction "3A1_9") (pintype "bidirectional"))
    )
    (net (code "205") (name "/VME_D1") (class "Default")
      (node (ref "IC25") (pin "12") (pinfunction "3A2_12") (pintype "bidirectional"))
    )
    (net (code "206") (name "/VME_D2") (class "Default")
      (node (ref "IC25") (pin "13") (pinfunction "3A3_13") (pintype "bidirectional"))
    )
    (net (code "207") (name "/VME_D3") (class "Default")
      (node (ref "IC25") (pin "16") (pinfunction "3A4_16") (pintype "bidirectional"))
    )
    (net (code "208") (name "/VME_D4") (class "Default")
      (node (ref "IC25") (pin "19") (pinfunction "3A5_19") (pintype "bidirectional"))
    )
    (net (code "209") (name "/VME_D5") (class "Default")
      (node (ref "IC25") (pin "20") (pinfunction "3A6_20") (pintype "bidirectional"))
    )
    (net (code "210") (name "/VME_D6") (class "Default")
      (node (ref "IC25") (pin "22") (pinfunction "3A7_22") (pintype "bidirectional"))
    )
    (net (code "211") (name "/VME_D7") (class "Default")
      (node (ref "IC25") (pin "23") (pinfunction "3A8_23") (pintype "bidirectional"))
    )
    (net (code "212") (name "/VME_D8") (class "Default")
      (node (ref "IC5") (pin "9") (pinfunction "3A1_9") (pintype "bidirectional"))
    )
    (net (code "213") (name "/VME_D9") (class "Default")
      (node (ref "IC5") (pin "12") (pinfunction "3A2_12") (pintype "bidirectional"))
    )
    (net (code "214") (name "/VME_D10") (class "Default")
      (node (ref "IC5") (pin "13") (pinfunction "3A3_13") (pintype "bidirectional"))
    )
    (net (code "215") (name "/VME_D11") (class "Default")
      (node (ref "IC5") (pin "16") (pinfunction "3A4_16") (pintype "bidirectional"))
    )
    (net (code "216") (name "/VME_D12") (class "Default")
      (node (ref "IC5") (pin "19") (pinfunction "3A5_19") (pintype "bidirectional"))
    )
    (net (code "217") (name "/VME_D13") (class "Default")
      (node (ref "IC5") (pin "20") (pinfunction "3A6_20") (pintype "bidirectional"))
    )
    (net (code "218") (name "/VME_D14") (class "Default")
      (node (ref "IC5") (pin "22") (pinfunction "3A7_22") (pintype "bidirectional"))
    )
    (net (code "219") (name "/VME_D15") (class "Default")
      (node (ref "IC5") (pin "23") (pinfunction "3A8_23") (pintype "bidirectional"))
    )
    (net (code "220") (name "/VME_D16") (class "Default")
      (node (ref "IC35") (pin "9") (pinfunction "3A1_9") (pintype "bidirectional"))
    )
    (net (code "221") (name "/VME_D17") (class "Default")
      (node (ref "IC35") (pin "12") (pinfunction "3A2_12") (pintype "bidirectional"))
    )
    (net (code "222") (name "/VME_D18") (class "Default")
      (node (ref "IC35") (pin "13") (pinfunction "3A3_13") (pintype "bidirectional"))
    )
    (net (code "223") (name "/VME_D19") (class "Default")
      (node (ref "IC35") (pin "16") (pinfunction "3A4_16") (pintype "bidirectional"))
    )
    (net (code "224") (name "/VME_D20") (class "Default")
      (node (ref "IC35") (pin "19") (pinfunction "3A5_19") (pintype "bidirectional"))
    )
    (net (code "225") (name "/VME_D21") (class "Default")
      (node (ref "IC35") (pin "20") (pinfunction "3A6_20") (pintype "bidirectional"))
    )
    (net (code "226") (name "/VME_D22") (class "Default")
      (node (ref "IC35") (pin "22") (pinfunction "3A7_22") (pintype "bidirectional"))
    )
    (net (code "227") (name "/VME_D23") (class "Default")
      (node (ref "IC35") (pin "23") (pinfunction "3A8_23") (pintype "bidirectional"))
    )
    (net (code "228") (name "/VME_D24") (class "Default")
      (node (ref "IC42") (pin "9") (pinfunction "3A1_9") (pintype "bidirectional"))
    )
    (net (code "229") (name "/VME_D25") (class "Default")
      (node (ref "IC42") (pin "12") (pinfunction "3A2_12") (pintype "bidirectional"))
    )
    (net (code "230") (name "/VME_D26") (class "Default")
      (node (ref "IC42") (pin "13") (pinfunction "3A3_13") (pintype "bidirectional"))
    )
    (net (code "231") (name "/VME_D27") (class "Default")
      (node (ref "IC42") (pin "16") (pinfunction "3A4_16") (pintype "bidirectional"))
    )
    (net (code "232") (name "/VME_D28") (class "Default")
      (node (ref "IC42") (pin "19") (pinfunction "3A5_19") (pintype "bidirectional"))
    )
    (net (code "233") (name "/VME_D29") (class "Default")
      (node (ref "IC42") (pin "20") (pinfunction "3A6_20") (pintype "bidirectional"))
    )
    (net (code "234") (name "/VME_D30") (class "Default")
      (node (ref "IC42") (pin "22") (pinfunction "3A7_22") (pintype "bidirectional"))
    )
    (net (code "235") (name "/VME_D31") (class "Default")
      (node (ref "IC42") (pin "23") (pinfunction "3A8_23") (pintype "bidirectional"))
    )
    (net (code "236") (name "/VME_DS1_N") (class "Default")
      (node (ref "IC22") (pin "3") (pinfunction "1Y_3") (pintype "output"))
    )
    (net (code "237") (name "/VME_DS2_N") (class "Default")
      (node (ref "IC22") (pin "6") (pinfunction "2Y_6") (pintype "output"))
    )
    (net (code "238") (name "/VME_DTACK_N") (class "Default")
      (node (ref "IC26") (pin "2") (pinfunction "1A_2") (pintype "input"))
      (node (ref "R158") (pin "2") (pinfunction "2_2") (pintype "passive"))
    )
    (net (code "239") (name "/VME_DTACK_OE") (class "Default")
      (node (ref "IC26") (pin "48") (pinfunction "1OEAB_48") (pintype "input"))
      (node (ref "R166") (pin "2") (pinfunction "2_2") (pintype "passive"))
    )
    (net (code "241") (name "/VME_D_DIR") (class "Default")
      (node (ref "IC25") (pin "24") (pinfunction "DIR_24") (pintype "input"))
      (node (ref "IC35") (pin "24") (pinfunction "DIR_24") (pintype "input"))
      (node (ref "IC42") (pin "24") (pinfunction "DIR_24") (pintype "input"))
      (node (ref "IC5") (pin "24") (pinfunction "DIR_24") (pintype "input"))
    )
    (net (code "242") (name "/VME_D_OE_N") (class "Default")
      (node (ref "IC35") (pin "14") (pinfunction "~{OE}_14") (pintype "input"))
      (node (ref "IC42") (pin "14") (pinfunction "~{OE}_14") (pintype "input"))
      (node (ref "IC5") (pin "14") (pinfunction "~{OE}_14") (pintype "input"))
      (node (ref "R157") (pin "2") (pinfunction "2_2") (pintype "passive"))
    )
    (net (code "243") (name "/VME_GA0") (class "Default")
      (node (ref "IC27") (pin "12") (pinfunction "3A2_12") (pintype "bidirectional"))
    )
    (net (code "244") (name "/VME_GA1") (class "Default")
      (node (ref "IC27") (pin "13") (pinfunction "3A3_13") (pintype "bidirectional"))
    )
    (net (code "245") (name "/VME_GA2") (class "Default")
      (node (ref "IC27") (pin "16") (pinfunction "3A4_16") (pintype "bidirectional"))
    )
    (net (code "246") (name "/VME_GA3") (class "Default")
      (node (ref "IC27") (pin "19") (pinfunction "3A5_19") (pintype "bidirectional"))
    )
    (net (code "247") (name "/VME_GA4") (class "Default")
      (node (ref "IC27") (pin "20") (pinfunction "3A6_20") (pintype "bidirectional"))
    )
    (net (code "248") (name "/VME_GAP") (class "Default")
      (node (ref "IC27") (pin "9") (pinfunction "3A1_9") (pintype "bidirectional"))
    )
    (net (code "250") (name "/VME_IACK") (class "Default")
      (node (ref "IC25") (pin "6") (pinfunction "2Y_6") (pintype "output"))
    )
    (net (code "251") (name "/VME_IACKIN_N") (class "Default")
      (node (ref "IC33") (pin "3") (pinfunction "1Y_3") (pintype "output"))
      (node (ref "R209") (pin "2") (pinfunction "2_2") (pintype "passive"))
    )
    (net (code "252") (name "/VME_IACKOUT_N") (class "Default")
      (node (ref "IC33") (pin "5") (pinfunction "2A_5") (pintype "input"))
      (node (ref "R209") (pin "1") (pinfunction "1_1") (pintype "passive"))
    )
    (net (code "253") (name "/VME_IRQ1") (class "Default")
      (node (ref "IC25") (pin "48") (pinfunction "1OEAB_48") (pintype "input"))
      (node (ref "R174") (pin "1") (pinfunction "1_1") (pintype "passive"))
    )
    (net (code "254") (name "/VME_IRQ2") (class "Default")
      (node (ref "IC5") (pin "41") (pinfunction "2OEAB_41") (pintype "input"))
      (node (ref "R191") (pin "1") (pinfunction "1_1") (pintype "passive"))
    )
    (net (code "255") (name "/VME_IRQ3") (class "Default")
      (node (ref "IC5") (pin "48") (pinfunction "1OEAB_48") (pintype "input"))
      (node (ref "R190") (pin "1") (pinfunction "1_1") (pintype "passive"))
    )
    (net (code "256") (name "/VME_IRQ4") (class "Default")
      (node (ref "IC42") (pin "41") (pinfunction "2OEAB_41") (pintype "input"))
      (node (ref "R185") (pin "1") (pinfunction "1_1") (pintype "passive"))
    )
    (net (code "257") (name "/VME_IRQ5") (class "Default")
      (node (ref "IC42") (pin "48") (pinfunction "1OEAB_48") (pintype "input"))
      (node (ref "R179") (pin "1") (pinfunction "1_1") (pintype "passive"))
    )
    (net (code "258") (name "/VME_IRQ6") (class "Default")
      (node (ref "IC35") (pin "41") (pinfunction "2OEAB_41") (pintype "input"))
      (node (ref "R177") (pin "1") (pinfunction "1_1") (pintype "passive"))
    )
    (net (code "259") (name "/VME_IRQ7") (class "Default")
      (node (ref "IC35") (pin "48") (pinfunction "1OEAB_48") (pintype "input"))
      (node (ref "R176") (pin "1") (pinfunction "1_1") (pintype "passive"))
    )
    (net (code "261") (name "/VME_LWORD") (class "Default")
      (node (ref "IC22") (pin "23") (pinfunction "3A8_23") (pintype "bidirectional"))
    )
    (net (code "262") (name "/VME_RETRY") (class "Default")
      (node (ref "IC15") (pin "2") (pinfunction "1A_2") (pintype "input"))
    )
    (net (code "263") (name "/VME_RETRY_OE") (class "Default")
      (node (ref "IC15") (pin "48") (pinfunction "1OEAB_48") (pintype "input"))
      (node (ref "R210") (pin "2") (pinfunction "2_2") (pintype "passive"))
    )
    (net (code "264") (name "/VME_SYSCLK") (class "Default")
      (node (ref "IC21") (pin "3") (pinfunction "1Y_3") (pintype "output"))
    )
    (net (code "265") (name "/VME_SYSRESET") (class "Default")
      (node (ref "IC15") (pin "22") (pinfunction "3A7_22") (pintype "bidirectional"))
    )
    (net (code "266") (name "/VME_TCK") (class "Default")
      (node (ref "IC15") (pin "23") (pinfunction "3A8_23") (pintype "bidirectional"))
    )
    (net (code "267") (name "/VME_TDI") (class "Default")
      (node (ref "IC27") (pin "22") (pinfunction "3A7_22") (pintype "bidirectional"))
    )
    (net (code "268") (name "/VME_TDO") (class "Default")
      (node (ref "IC27") (pin "5") (pinfunction "2A_5") (pintype "input"))
    )
    (net (code "269") (name "/VME_TDO_OE") (class "Default")
      (node (ref "IC27") (pin "41") (pinfunction "2OEAB_41") (pintype "input"))
    )
    (net (code "270") (name "/VME_TMS") (class "Default")
      (node (ref "IC27") (pin "23") (pinfunction "3A8_23") (pintype "bidirectional"))
    )
    (net (code "271") (name "/VME_TRST") (class "Default")
      (node (ref "IC27") (pin "3") (pinfunction "1Y_3") (pintype "output"))
    )
    (net (code "272") (name "/VME_WRITE") (class "Default")
      (node (ref "IC26") (pin "6") (pinfunction "2Y_6") (pintype "output"))
    )
    (net (code "273") (name "GND") (class "Default")
      (node (ref "C125") (pin "2") (pinfunction "2_2") (pintype "passive"))
      (node (ref "C127") (pin "2") (pinfunction "2_2") (pintype "passive"))
      (node (ref "C132") (pin "2") (pinfunction "2_2") (pintype "passive"))
      (node (ref "C153") (pin "2") (pinfunction "2_2") (pintype "passive"))
      (node (ref "C154") (pin "1") (pinfunction "1_1") (pintype "passive"))
      (node (ref "C164") (pin "2") (pinfunction "2_2") (pintype "passive"))
      (node (ref "C184") (pin "1") (pinfunction "1_1") (pintype "passive"))
      (node (ref "C185") (pin "2") (pinfunction "2_2") (pintype "passive"))
      (node (ref "C226") (pin "1") (pinfunction "1_1") (pintype "passive"))
      (node (ref "C227") (pin "1") (pinfunction "1_1") (pintype "passive"))
      (node (ref "C240") (pin "2") (pinfunction "2_2") (pintype "passive"))
      (node (ref "C244") (pin "1") (pinfunction "1_1") (pintype "passive"))
      (node (ref "C245") (pin "1") (pinfunction "1_1") (pintype "passive"))
      (node (ref "C246") (pin "1") (pinfunction "1_1") (pintype "passive"))
      (node (ref "C247") (pin "2") (pinfunction "2_2") (pintype "passive"))
      (node (ref "C248") (pin "2") (pinfunction "2_2") (pintype "passive"))
      (node (ref "C249") (pin "2") (pinfunction "2_2") (pintype "passive"))
      (node (ref "C250") (pin "1") (pinfunction "1_1") (pintype "passive"))
      (node (ref "C251") (pin "1") (pinfunction "1_1") (pintype "passive"))
      (node (ref "C252") (pin "1") (pinfunction "1_1") (pintype "passive"))
      (node (ref "C253") (pin "2") (pinfunction "2_2") (pintype "passive"))
      (node (ref "C254") (pin "1") (pinfunction "1_1") (pintype "passive"))
      (node (ref "C257") (pin "1") (pinfunction "1_1") (pintype "passive"))
      (node (ref "C264") (pin "2") (pinfunction "2_2") (pintype "passive"))
      (node (ref "C287") (pin "2") (pinfunction "2_2") (pintype "passive"))
      (node (ref "C292") (pin "1") (pinfunction "1_1") (pintype "passive"))
      (node (ref "C293") (pin "1") (pinfunction "1_1") (pintype "passive"))
      (node (ref "C294") (pin "2") (pinfunction "2_2") (pintype "passive"))
      (node (ref "C295") (pin "1") (pinfunction "1_1") (pintype "passive"))
      (node (ref "C296") (pin "2") (pinfunction "2_2") (pintype "passive"))
      (node (ref "C318") (pin "1") (pinfunction "1_1") (pintype "passive"))
      (node (ref "C319") (pin "2") (pinfunction "2_2") (pintype "passive"))
      (node (ref "C326") (pin "2") (pinfunction "2_2") (pintype "passive"))
      (node (ref "C327") (pin "1") (pinfunction "1_1") (pintype "passive"))
      (node (ref "C328") (pin "2") (pinfunction "2_2") (pintype "passive"))
      (node (ref "C329") (pin "1") (pinfunction "1_1") (pintype "passive"))
      (node (ref "C331") (pin "2") (pinfunction "2_2") (pintype "passive"))
      (node (ref "C332") (pin "1") (pinfunction "1_1") (pintype "passive"))
      (node (ref "C335") (pin "1") (pinfunction "1_1") (pintype "passive"))
      (node (ref "C336") (pin "2") (pinfunction "2_2") (pintype "passive"))
      (node (ref "C337") (pin "1") (pinfunction "1_1") (pintype "passive"))
      (node (ref "C338") (pin "2") (pinfunction "2_2") (pintype "passive"))
      (node (ref "C436") (pin "2") (pinfunction "2_2") (pintype "passive"))
      (node (ref "C437") (pin "1") (pinfunction "1_1") (pintype "passive"))
      (node (ref "C447") (pin "2") (pinfunction "2_2") (pintype "passive"))
      (node (ref "C457") (pin "1") (pinfunction "1_1") (pintype "passive"))
      (node (ref "C464") (pin "2") (pinfunction "2_2") (pintype "passive"))
      (node (ref "C465") (pin "1") (pinfunction "1_1") (pintype "passive"))
      (node (ref "C500") (pin "1") (pinfunction "1_1") (pintype "passive"))
      (node (ref "C501") (pin "2") (pinfunction "2_2") (pintype "passive"))
      (node (ref "C506") (pin "1") (pinfunction "1_1") (pintype "passive"))
      (node (ref "C507") (pin "2") (pinfunction "2_2") (pintype "passive"))
      (node (ref "C512") (pin "1") (pinfunction "1_1") (pintype "passive"))
      (node (ref "C513") (pin "2") (pinfunction "2_2") (pintype "passive"))
      (node (ref "C516") (pin "1") (pinfunction "1_1") (pintype "passive"))
      (node (ref "C517") (pin "2") (pinfunction "2_2") (pintype "passive"))
      (node (ref "C519") (pin "2") (pinfunction "2_2") (pintype "passive"))
      (node (ref "C520") (pin "1") (pinfunction "1_1") (pintype "passive"))
      (node (ref "C521") (pin "2") (pinfunction "2_2") (pintype "passive"))
      (node (ref "C522") (pin "1") (pinfunction "1_1") (pintype "passive"))
      (node (ref "IC15") (pin "10") (pinfunction "GND_10") (pintype "power_in"))
      (node (ref "IC15") (pin "14") (pinfunction "~{OE}_14") (pintype "input"))
      (node (ref "IC15") (pin "15") (pinfunction "GND_15") (pintype "power_in"))
      (node (ref "IC15") (pin "17") (pinfunction "CLKBA_17") (pintype "input"))
      (node (ref "IC15") (pin "21") (pinfunction "GND_21") (pintype "power_in"))
      (node (ref "IC15") (pin "24") (pinfunction "DIR_24") (pintype "input"))
      (node (ref "IC15") (pin "28") (pinfunction "GND_28") (pintype "power_in"))
      (node (ref "IC15") (pin "32") (pinfunction "CLKAB_32") (pintype "input"))
      (node (ref "IC15") (pin "34") (pinfunction "GND_34") (pintype "power_in"))
      (node (ref "IC15") (pin "39") (pinfunction "GND_39") (pintype "power_in"))
      (node (ref "IC15") (pin "4") (pinfunction "GND_4") (pintype "power_in"))
      (node (ref "IC15") (pin "45") (pinfunction "GND_45") (pintype "input"))
      (node (ref "IC15") (pin "5") (pinfunction "2A_5") (pintype "input"))
      (node (ref "IC21") (pin "1") (pinfunction "~{1OEBY}_1") (pintype "input"))
      (node (ref "IC21") (pin "10") (pinfunction "GND_10") (pintype "power_in"))
      (node (ref "IC21") (pin "15") (pinfunction "GND_15") (pintype "power_in"))
      (node (ref "IC21") (pin "17") (pinfunction "CLKBA_17") (pintype "input"))
      (node (ref "IC21") (pin "2") (pinfunction "1A_2") (pintype "input"))
      (node (ref "IC21") (pin "21") (pinfunction "GND_21") (pintype "power_in"))
      (node (ref "IC21") (pin "28") (pinfunction "GND_28") (pintype "power_in"))
      (node (ref "IC21") (pin "32") (pinfunction "CLKAB_32") (pintype "input"))
      (node (ref "IC21") (pin "34") (pinfunction "GND_34") (pintype "power_in"))
      (node (ref "IC21") (pin "39") (pinfunction "GND_39") (pintype "power_in"))
      (node (ref "IC21") (pin "4") (pinfunction "GND_4") (pintype "power_in"))
      (node (ref "IC21") (pin "41") (pinfunction "2OEAB_41") (pintype "input"))
      (node (ref "IC21") (pin "45") (pinfunction "GND_45") (pintype "input"))
      (node (ref "IC21") (pin "48") (pinfunction "1OEAB_48") (pintype "input"))
      (node (ref "IC21") (pin "5") (pinfunction "2A_5") (pintype "input"))
      (node (ref "IC21") (pin "8") (pinfunction "2~{OEBY}_8") (pintype "input"))
      (node (ref "IC22") (pin "1") (pinfunction "~{1OEBY}_1") (pintype "input"))
      (node (ref "IC22") (pin "10") (pinfunction "GND_10") (pintype "power_in"))
      (node (ref "IC22") (pin "15") (pinfunction "GND_15") (pintype "power_in"))
      (node (ref "IC22") (pin "17") (pinfunction "CLKBA_17") (pintype "input"))
      (node (ref "IC22") (pin "2") (pinfunction "1A_2") (pintype "input"))
      (node (ref "IC22") (pin "21") (pinfunction "GND_21") (pintype "power_in"))
      (node (ref "IC22") (pin "28") (pinfunction "GND_28") (pintype "power_in"))
      (node (ref "IC22") (pin "32") (pinfunction "CLKAB_32") (pintype "input"))
      (node (ref "IC22") (pin "34") (pinfunction "GND_34") (pintype "power_in"))
      (node (ref "IC22") (pin "39") (pinfunction "GND_39") (pintype "power_in"))
      (node (ref "IC22") (pin "4") (pinfunction "GND_4") (pintype "power_in"))
      (node (ref "IC22") (pin "41") (pinfunction "2OEAB_41") (pintype "input"))
      (node (ref "IC22") (pin "45") (pinfunction "GND_45") (pintype "input"))
      (node (ref "IC22") (pin "48") (pinfunction "1OEAB_48") (pintype "input"))
      (node (ref "IC22") (pin "5") (pinfunction "2A_5") (pintype "input"))
      (node (ref "IC22") (pin "8") (pinfunction "2~{OEBY}_8") (pintype "input"))
      (node (ref "IC25") (pin "10") (pinfunction "GND_10") (pintype "power_in"))
      (node (ref "IC25") (pin "15") (pinfunction "GND_15") (pintype "power_in"))
      (node (ref "IC25") (pin "17") (pinfunction "CLKBA_17") (pintype "input"))
      (node (ref "IC25") (pin "2") (pinfunction "1A_2") (pintype "input"))
      (node (ref "IC25") (pin "21") (pinfunction "GND_21") (pintype "power_in"))
      (node (ref "IC25") (pin "28") (pinfunction "GND_28") (pintype "power_in"))
      (node (ref "IC25") (pin "32") (pinfunction "CLKAB_32") (pintype "input"))
      (node (ref "IC25") (pin "34") (pinfunction "GND_34") (pintype "power_in"))
      (node (ref "IC25") (pin "39") (pinfunction "GND_39") (pintype "power_in"))
      (node (ref "IC25") (pin "4") (pinfunction "GND_4") (pintype "power_in"))
      (node (ref "IC25") (pin "41") (pinfunction "2OEAB_41") (pintype "input"))
      (node (ref "IC25") (pin "45") (pinfunction "GND_45") (pintype "input"))
      (node (ref "IC25") (pin "5") (pinfunction "2A_5") (pintype "input"))
      (node (ref "IC25") (pin "8") (pinfunction "2~{OEBY}_8") (pintype "input"))
      (node (ref "IC26") (pin "10") (pinfunction "GND_10") (pintype "power_in"))
      (node (ref "IC26") (pin "15") (pinfunction "GND_15") (pintype "power_in"))
      (node (ref "IC26") (pin "17") (pinfunction "CLKBA_17") (pintype "input"))
      (node (ref "IC26") (pin "21") (pinfunction "GND_21") (pintype "power_in"))
      (node (ref "IC26") (pin "28") (pinfunction "GND_28") (pintype "power_in"))
      (node (ref "IC26") (pin "32") (pinfunction "CLKAB_32") (pintype "input"))
      (node (ref "IC26") (pin "34") (pinfunction "GND_34") (pintype "power_in"))
      (node (ref "IC26") (pin "39") (pinfunction "GND_39") (pintype "power_in"))
      (node (ref "IC26") (pin "4") (pinfunction "GND_4") (pintype "power_in"))
      (node (ref "IC26") (pin "41") (pinfunction "2OEAB_41") (pintype "input"))
      (node (ref "IC26") (pin "45") (pinfunction "GND_45") (pintype "input"))
      (node (ref "IC26") (pin "5") (pinfunction "2A_5") (pintype "input"))
      (node (ref "IC26") (pin "8") (pinfunction "2~{OEBY}_8") (pintype "input"))
      (node (ref "IC27") (pin "1") (pinfunction "~{1OEBY}_1") (pintype "input"))
      (node (ref "IC27") (pin "10") (pinfunction "GND_10") (pintype "power_in"))
      (node (ref "IC27") (pin "14") (pinfunction "~{OE}_14") (pintype "input"))
      (node (ref "IC27") (pin "15") (pinfunction "GND_15") (pintype "power_in"))
      (node (ref "IC27") (pin "17") (pinfunction "CLKBA_17") (pintype "input"))
      (node (ref "IC27") (pin "2") (pinfunction "1A_2") (pintype "input"))
      (node (ref "IC27") (pin "21") (pinfunction "GND_21") (pintype "power_in"))
      (node (ref "IC27") (pin "24") (pinfunction "DIR_24") (pintype "input"))
      (node (ref "IC27") (pin "28") (pinfunction "GND_28") (pintype "power_in"))
      (node (ref "IC27") (pin "32") (pinfunction "CLKAB_32") (pintype "input"))
      (node (ref "IC27") (pin "34") (pinfunction "GND_34") (pintype "power_in"))
      (node (ref "IC27") (pin "39") (pinfunction "GND_39") (pintype "power_in"))
      (node (ref "IC27") (pin "4") (pinfunction "GND_4") (pintype "power_in"))
      (node (ref "IC27") (pin "45") (pinfunction "GND_45") (pintype "input"))
      (node (ref "IC27") (pin "48") (pinfunction "1OEAB_48") (pintype "input"))
      (node (ref "IC33") (pin "1") (pinfunction "~{1OEBY}_1") (pintype "input"))
      (node (ref "IC33") (pin "10") (pinfunction "GND_10") (pintype "power_in"))
      (node (ref "IC33") (pin "15") (pinfunction "GND_15") (pintype "power_in"))
      (node (ref "IC33") (pin "17") (pinfunction "CLKBA_17") (pintype "input"))
      (node (ref "IC33") (pin "2") (pinfunction "1A_2") (pintype "input"))
      (node (ref "IC33") (pin "21") (pinfunction "GND_21") (pintype "power_in"))
      (node (ref "IC33") (pin "28") (pinfunction "GND_28") (pintype "power_in"))
      (node (ref "IC33") (pin "32") (pinfunction "CLKAB_32") (pintype "input"))
      (node (ref "IC33") (pin "34") (pinfunction "GND_34") (pintype "power_in"))
      (node (ref "IC33") (pin "39") (pinfunction "GND_39") (pintype "power_in"))
      (node (ref "IC33") (pin "4") (pinfunction "GND_4") (pintype "power_in"))
      (node (ref "IC33") (pin "45") (pinfunction "GND_45") (pintype "input"))
      (node (ref "IC33") (pin "48") (pinfunction "1OEAB_48") (pintype "input"))
      (node (ref "IC35") (pin "10") (pinfunction "GND_10") (pintype "power_in"))
      (node (ref "IC35") (pin "15") (pinfunction "GND_15") (pintype "power_in"))
      (node (ref "IC35") (pin "17") (pinfunction "CLKBA_17") (pintype "input"))
      (node (ref "IC35") (pin "2") (pinfunction "1A_2") (pintype "input"))
      (node (ref "IC35") (pin "21") (pinfunction "GND_21") (pintype "power_in"))
      (node (ref "IC35") (pin "28") (pinfunction "GND_28") (pintype "power_in"))
      (node (ref "IC35") (pin "32") (pinfunction "CLKAB_32") (pintype "input"))
      (node (ref "IC35") (pin "34") (pinfunction "GND_34") (pintype "power_in"))
      (node (ref "IC35") (pin "39") (pinfunction "GND_39") (pintype "power_in"))
      (node (ref "IC35") (pin "4") (pinfunction "GND_4") (pintype "power_in"))
      (node (ref "IC35") (pin "45") (pinfunction "GND_45") (pintype "input"))
      (node (ref "IC35") (pin "5") (pinfunction "2A_5") (pintype "input"))
      (node (ref "IC42") (pin "10") (pinfunction "GND_10") (pintype "power_in"))
      (node (ref "IC42") (pin "15") (pinfunction "GND_15") (pintype "power_in"))
      (node (ref "IC42") (pin "17") (pinfunction "CLKBA_17") (pintype "input"))
      (node (ref "IC42") (pin "2") (pinfunction "1A_2") (pintype "input"))
      (node (ref "IC42") (pin "21") (pinfunction "GND_21") (pintype "power_in"))
      (node (ref "IC42") (pin "28") (pinfunction "GND_28") (pintype "power_in"))
      (node (ref "IC42") (pin "32") (pinfunction "CLKAB_32") (pintype "input"))
      (node (ref "IC42") (pin "34") (pinfunction "GND_34") (pintype "power_in"))
      (node (ref "IC42") (pin "39") (pinfunction "GND_39") (pintype "power_in"))
      (node (ref "IC42") (pin "4") (pinfunction "GND_4") (pintype "power_in"))
      (node (ref "IC42") (pin "45") (pinfunction "GND_45") (pintype "input"))
      (node (ref "IC42") (pin "5") (pinfunction "2A_5") (pintype "input"))
      (node (ref "IC5") (pin "10") (pinfunction "GND_10") (pintype "power_in"))
      (node (ref "IC5") (pin "15") (pinfunction "GND_15") (pintype "power_in"))
      (node (ref "IC5") (pin "17") (pinfunction "CLKBA_17") (pintype "input"))
      (node (ref "IC5") (pin "2") (pinfunction "1A_2") (pintype "input"))
      (node (ref "IC5") (pin "21") (pinfunction "GND_21") (pintype "power_in"))
      (node (ref "IC5") (pin "28") (pinfunction "GND_28") (pintype "power_in"))
      (node (ref "IC5") (pin "32") (pinfunction "CLKAB_32") (pintype "input"))
      (node (ref "IC5") (pin "34") (pinfunction "GND_34") (pintype "power_in"))
      (node (ref "IC5") (pin "39") (pinfunction "GND_39") (pintype "power_in"))
      (node (ref "IC5") (pin "4") (pinfunction "GND_4") (pintype "power_in"))
      (node (ref "IC5") (pin "45") (pinfunction "GND_45") (pintype "input"))
      (node (ref "IC5") (pin "5") (pinfunction "2A_5") (pintype "input"))
      (node (ref "P1") (pin "MTG1") (pinfunction "MTG1_MTG1") (pintype "passive"))
      (node (ref "P1") (pin "MTG2") (pinfunction "MTG2_MTG2") (pintype "passive"))
      (node (ref "P1") (pin "a11") (pinfunction "a11_a11") (pintype "bidirectional"))
      (node (ref "P1") (pin "a15") (pinfunction "a15_a15") (pintype "bidirectional"))
      (node (ref "P1") (pin "a17") (pinfunction "a17_a17") (pintype "bidirectional"))
      (node (ref "P1") (pin "a19") (pinfunction "a19_a19") (pintype "bidirectional"))
      (node (ref "P1") (pin "a9") (pinfunction "a9_a9") (pintype "bidirectional"))
      (node (ref "P1") (pin "b20") (pinfunction "b20_b20") (pintype "bidirectional"))
      (node (ref "P1") (pin "b23") (pinfunction "b23_b23") (pintype "bidirectional"))
      (node (ref "P1") (pin "c9") (pinfunction "c9_c9") (pintype "bidirectional"))
      (node (ref "P1") (pin "d2") (pinfunction "d2_d2") (pintype "bidirectional"))
      (node (ref "P1") (pin "d31") (pinfunction "d31_d31") (pintype "bidirectional"))
      (node (ref "P1") (pin "z10") (pinfunction "z10_z10") (pintype "bidirectional"))
      (node (ref "P1") (pin "z12") (pinfunction "z12_z12") (pintype "bidirectional"))
      (node (ref "P1") (pin "z14") (pinfunction "z14_z14") (pintype "bidirectional"))
      (node (ref "P1") (pin "z16") (pinfunction "z16_z16") (pintype "bidirectional"))
      (node (ref "P1") (pin "z18") (pinfunction "z18_z18") (pintype "bidirectional"))
      (node (ref "P1") (pin "z2") (pinfunction "z2_z2") (pintype "bidirectional"))
      (node (ref "P1") (pin "z20") (pinfunction "z20_z20") (pintype "bidirectional"))
      (node (ref "P1") (pin "z22") (pinfunction "z22_z22") (pintype "bidirectional"))
      (node (ref "P1") (pin "z24") (pinfunction "z24_z24") (pintype "bidirectional"))
      (node (ref "P1") (pin "z26") (pinfunction "z26_z26") (pintype "bidirectional"))
      (node (ref "P1") (pin "z28") (pinfunction "z28_z28") (pintype "bidirectional"))
      (node (ref "P1") (pin "z30") (pinfunction "z30_z30") (pintype "bidirectional"))
      (node (ref "P1") (pin "z32") (pinfunction "z32_z32") (pintype "bidirectional"))
      (node (ref "P1") (pin "z4") (pinfunction "z4_z4") (pintype "bidirectional"))
      (node (ref "P1") (pin "z6") (pinfunction "z6_z6") (pintype "bidirectional"))
      (node (ref "P1") (pin "z8") (pinfunction "z8_z8") (pintype "bidirectional"))
      (node (ref "P3") (pin "MTG1") (pinfunction "MTG1_MTG1") (pintype "passive"))
      (node (ref "P3") (pin "MTG2") (pinfunction "MTG2_MTG2") (pintype "passive"))
      (node (ref "P3") (pin "a1") (pinfunction "a1_a1") (pintype "bidirectional"))
      (node (ref "P3") (pin "a10") (pinfunction "a10_a10") (pintype "bidirectional"))
      (node (ref "P3") (pin "a13") (pinfunction "a13_a13") (pintype "bidirectional"))
      (node (ref "P3") (pin "a16") (pinfunction "a16_a16") (pintype "bidirectional"))
      (node (ref "P3") (pin "a19") (pinfunction "a19_a19") (pintype "bidirectional"))
      (node (ref "P3") (pin "a22") (pinfunction "a22_a22") (pintype "bidirectional"))
      (node (ref "P3") (pin "a25") (pinfunction "a25_a25") (pintype "bidirectional"))
      (node (ref "P3") (pin "a28") (pinfunction "a28_a28") (pintype "bidirectional"))
      (node (ref "P3") (pin "a31") (pinfunction "a31_a31") (pintype "bidirectional"))
      (node (ref "P3") (pin "a32") (pinfunction "a32_a32") (pintype "bidirectional"))
      (node (ref "P3") (pin "a4") (pinfunction "a4_a4") (pintype "bidirectional"))
      (node (ref "P3") (pin "a7") (pinfunction "a7_a7") (pintype "bidirectional"))
      (node (ref "P3") (pin "b12") (pinfunction "b12_b12") (pintype "bidirectional"))
      (node (ref "P3") (pin "b2") (pinfunction "b2_b2") (pintype "bidirectional"))
      (node (ref "P3") (pin "b22") (pinfunction "b22_b22") (pintype "bidirectional"))
      (node (ref "P3") (pin "b31") (pinfunction "b31_b31") (pintype "bidirectional"))
      (node (ref "P3") (pin "c23") (pinfunction "c23_c23") (pintype "bidirectional"))
      (node (ref "P3") (pin "c24") (pinfunction "c24_c24") (pintype "bidirectional"))
      (node (ref "P3") (pin "c27") (pinfunction "c27_c27") (pintype "bidirectional"))
      (node (ref "P3") (pin "c28") (pinfunction "c28_c28") (pintype "bidirectional"))
      (node (ref "P3") (pin "c31") (pinfunction "c31_c31") (pintype "bidirectional"))
      (node (ref "P3") (pin "c32") (pinfunction "c32_c32") (pintype "bidirectional"))
      (node (ref "P3") (pin "d1") (pinfunction "d1_d1") (pintype "bidirectional"))
      (node (ref "P3") (pin "d10") (pinfunction "d10_d10") (pintype "bidirectional"))
      (node (ref "P3") (pin "d13") (pinfunction "d13_d13") (pintype "bidirectional"))
      (node (ref "P3") (pin "d16") (pinfunction "d16_d16") (pintype "bidirectional"))
      (node (ref "P3") (pin "d19") (pinfunction "d19_d19") (pintype "bidirectional"))
      (node (ref "P3") (pin "d22") (pinfunction "d22_d22") (pintype "bidirectional"))
      (node (ref "P3") (pin "d25") (pinfunction "d25_d25") (pintype "bidirectional"))
      (node (ref "P3") (pin "d28") (pinfunction "d28_d28") (pintype "bidirectional"))
      (node (ref "P3") (pin "d31") (pinfunction "d31_d31") (pintype "bidirectional"))
      (node (ref "P3") (pin "d4") (pinfunction "d4_d4") (pintype "bidirectional"))
      (node (ref "P3") (pin "d7") (pinfunction "d7_d7") (pintype "bidirectional"))
      (node (ref "P3") (pin "z10") (pinfunction "z10_z10") (pintype "bidirectional"))
      (node (ref "P3") (pin "z12") (pinfunction "z12_z12") (pintype "bidirectional"))
      (node (ref "P3") (pin "z14") (pinfunction "z14_z14") (pintype "bidirectional"))
      (node (ref "P3") (pin "z16") (pinfunction "z16_z16") (pintype "bidirectional"))
      (node (ref "P3") (pin "z18") (pinfunction "z18_z18") (pintype "bidirectional"))
      (node (ref "P3") (pin "z2") (pinfunction "z2_z2") (pintype "bidirectional"))
      (node (ref "P3") (pin "z20") (pinfunction "z20_z20") (pintype "bidirectional"))
      (node (ref "P3") (pin "z22") (pinfunction "z22_z22") (pintype "bidirectional"))
      (node (ref "P3") (pin "z24") (pinfunction "z24_z24") (pintype "bidirectional"))
      (node (ref "P3") (pin "z26") (pinfunction "z26_z26") (pintype "bidirectional"))
      (node (ref "P3") (pin "z28") (pinfunction "z28_z28") (pintype "bidirectional"))
      (node (ref "P3") (pin "z30") (pinfunction "z30_z30") (pintype "bidirectional"))
      (node (ref "P3") (pin "z32") (pinfunction "z32_z32") (pintype "bidirectional"))
      (node (ref "P3") (pin "z4") (pinfunction "z4_z4") (pintype "bidirectional"))
      (node (ref "P3") (pin "z6") (pinfunction "z6_z6") (pintype "bidirectional"))
      (node (ref "P3") (pin "z8") (pinfunction "z8_z8") (pintype "bidirectional"))
      (node (ref "R166") (pin "1") (pinfunction "1_1") (pintype "passive"))
      (node (ref "R174") (pin "2") (pinfunction "2_2") (pintype "passive"))
      (node (ref "R176") (pin "2") (pinfunction "2_2") (pintype "passive"))
      (node (ref "R177") (pin "2") (pinfunction "2_2") (pintype "passive"))
      (node (ref "R179") (pin "2") (pinfunction "2_2") (pintype "passive"))
      (node (ref "R185") (pin "2") (pinfunction "2_2") (pintype "passive"))
      (node (ref "R190") (pin "2") (pinfunction "2_2") (pintype "passive"))
      (node (ref "R191") (pin "2") (pinfunction "2_2") (pintype "passive"))
      (node (ref "R210") (pin "1") (pinfunction "1_1") (pintype "passive"))
      (node (ref "R211") (pin "1") (pinfunction "1_1") (pintype "passive"))
    )
    (net (code "274") (name "M12V_VME") (class "Default")
      (node (ref "P1") (pin "a31") (pinfunction "a31_a31") (pintype "bidirectional"))
    )
    (net (code "275") (name "P3V3") (class "Default")
      (node (ref "C125") (pin "1") (pinfunction "1_1") (pintype "passive"))
      (node (ref "C127") (pin "1") (pinfunction "1_1") (pintype "passive"))
      (node (ref "C132") (pin "1") (pinfunction "1_1") (pintype "passive"))
      (node (ref "C153") (pin "1") (pinfunction "1_1") (pintype "passive"))
      (node (ref "C154") (pin "2") (pinfunction "2_2") (pintype "passive"))
      (node (ref "C164") (pin "1") (pinfunction "1_1") (pintype "passive"))
      (node (ref "C184") (pin "2") (pinfunction "2_2") (pintype "passive"))
      (node (ref "C185") (pin "1") (pinfunction "1_1") (pintype "passive"))
      (node (ref "C226") (pin "2") (pinfunction "2_2") (pintype "passive"))
      (node (ref "C227") (pin "2") (pinfunction "2_2") (pintype "passive"))
      (node (ref "C240") (pin "1") (pinfunction "1_1") (pintype "passive"))
      (node (ref "C244") (pin "2") (pinfunction "2_2") (pintype "passive"))
      (node (ref "C245") (pin "2") (pinfunction "2_2") (pintype "passive"))
      (node (ref "C246") (pin "2") (pinfunction "2_2") (pintype "passive"))
      (node (ref "C247") (pin "1") (pinfunction "1_1") (pintype "passive"))
      (node (ref "C248") (pin "1") (pinfunction "1_1") (pintype "passive"))
      (node (ref "C249") (pin "1") (pinfunction "1_1") (pintype "passive"))
      (node (ref "C250") (pin "2") (pinfunction "2_2") (pintype "passive"))
      (node (ref "C251") (pin "2") (pinfunction "2_2") (pintype "passive"))
      (node (ref "C252") (pin "2") (pinfunction "2_2") (pintype "passive"))
      (node (ref "C253") (pin "1") (pinfunction "1_1") (pintype "passive"))
      (node (ref "C254") (pin "2") (pinfunction "2_2") (pintype "passive"))
      (node (ref "C257") (pin "2") (pinfunction "2_2") (pintype "passive"))
      (node (ref "C264") (pin "1") (pinfunction "1_1") (pintype "passive"))
      (node (ref "C287") (pin "1") (pinfunction "1_1") (pintype "passive"))
      (node (ref "C292") (pin "2") (pinfunction "2_2") (pintype "passive"))
      (node (ref "C293") (pin "2") (pinfunction "2_2") (pintype "passive"))
      (node (ref "C294") (pin "1") (pinfunction "1_1") (pintype "passive"))
      (node (ref "C295") (pin "2") (pinfunction "2_2") (pintype "passive"))
      (node (ref "C296") (pin "1") (pinfunction "1_1") (pintype "passive"))
      (node (ref "C318") (pin "2") (pinfunction "2_2") (pintype "passive"))
      (node (ref "C319") (pin "1") (pinfunction "1_1") (pintype "passive"))
      (node (ref "C326") (pin "1") (pinfunction "1_1") (pintype "passive"))
      (node (ref "C327") (pin "2") (pinfunction "2_2") (pintype "passive"))
      (node (ref "C328") (pin "1") (pinfunction "1_1") (pintype "passive"))
      (node (ref "C329") (pin "2") (pinfunction "2_2") (pintype "passive"))
      (node (ref "C331") (pin "1") (pinfunction "1_1") (pintype "passive"))
      (node (ref "C332") (pin "2") (pinfunction "2_2") (pintype "passive"))
      (node (ref "C335") (pin "2") (pinfunction "2_2") (pintype "passive"))
      (node (ref "C336") (pin "1") (pinfunction "1_1") (pintype "passive"))
      (node (ref "C337") (pin "2") (pinfunction "2_2") (pintype "passive"))
      (node (ref "C338") (pin "1") (pinfunction "1_1") (pintype "passive"))
      (node (ref "C436") (pin "1") (pinfunction "1_1") (pintype "passive"))
      (node (ref "C437") (pin "2") (pinfunction "2_2") (pintype "passive"))
      (node (ref "C447") (pin "1") (pinfunction "1_1") (pintype "passive"))
      (node (ref "C457") (pin "2") (pinfunction "2_2") (pintype "passive"))
      (node (ref "C464") (pin "1") (pinfunction "1_1") (pintype "passive"))
      (node (ref "C465") (pin "2") (pinfunction "2_2") (pintype "passive"))
      (node (ref "C500") (pin "2") (pinfunction "2_2") (pintype "passive"))
      (node (ref "C501") (pin "1") (pinfunction "1_1") (pintype "passive"))
      (node (ref "C506") (pin "2") (pinfunction "2_2") (pintype "passive"))
      (node (ref "C507") (pin "1") (pinfunction "1_1") (pintype "passive"))
      (node (ref "C512") (pin "2") (pinfunction "2_2") (pintype "passive"))
      (node (ref "C513") (pin "1") (pinfunction "1_1") (pintype "passive"))
      (node (ref "C516") (pin "2") (pinfunction "2_2") (pintype "passive"))
      (node (ref "C517") (pin "1") (pinfunction "1_1") (pintype "passive"))
      (node (ref "C519") (pin "1") (pinfunction "1_1") (pintype "passive"))
      (node (ref "C520") (pin "2") (pinfunction "2_2") (pintype "passive"))
      (node (ref "C521") (pin "1") (pinfunction "1_1") (pintype "passive"))
      (node (ref "C522") (pin "2") (pinfunction "2_2") (pintype "passive"))
      (node (ref "IC15") (pin "1") (pinfunction "~{1OEBY}_1") (pintype "input"))
      (node (ref "IC15") (pin "11") (pinfunction "LE_11") (pintype "input"))
      (node (ref "IC15") (pin "18") (pinfunction "VCC_18") (pintype "power_in"))
      (node (ref "IC15") (pin "25") (pinfunction "VCC_25") (pintype "power_in"))
      (node (ref "IC15") (pin "31") (pinfunction "VCC_31") (pintype "power_in"))
      (node (ref "IC15") (pin "35") (pinfunction "VCC_35") (pintype "power_in"))
      (node (ref "IC15") (pin "38") (pinfunction "VCC_38") (pintype "power_in"))
      (node (ref "IC15") (pin "42") (pinfunction "VCC_42") (pintype "power_in"))
      (node (ref "IC15") (pin "44") (pinfunction "BIASVCC_44") (pintype "input"))
      (node (ref "IC15") (pin "47") (pinfunction "VCC_47") (pintype "input"))
      (node (ref "IC15") (pin "7") (pinfunction "VCC_7") (pintype "power_in"))
      (node (ref "IC15") (pin "8") (pinfunction "2~{OEBY}_8") (pintype "input"))
      (node (ref "IC21") (pin "11") (pinfunction "LE_11") (pintype "input"))
      (node (ref "IC21") (pin "18") (pinfunction "VCC_18") (pintype "power_in"))
      (node (ref "IC21") (pin "25") (pinfunction "VCC_25") (pintype "power_in"))
      (node (ref "IC21") (pin "31") (pinfunction "VCC_31") (pintype "power_in"))
      (node (ref "IC21") (pin "35") (pinfunction "VCC_35") (pintype "power_in"))
      (node (ref "IC21") (pin "38") (pinfunction "VCC_38") (pintype "power_in"))
      (node (ref "IC21") (pin "42") (pinfunction "VCC_42") (pintype "power_in"))
      (node (ref "IC21") (pin "44") (pinfunction "BIASVCC_44") (pintype "input"))
      (node (ref "IC21") (pin "47") (pinfunction "VCC_47") (pintype "input"))
      (node (ref "IC21") (pin "7") (pinfunction "VCC_7") (pintype "power_in"))
      (node (ref "IC22") (pin "11") (pinfunction "LE_11") (pintype "input"))
      (node (ref "IC22") (pin "18") (pinfunction "VCC_18") (pintype "power_in"))
      (node (ref "IC22") (pin "25") (pinfunction "VCC_25") (pintype "power_in"))
      (node (ref "IC22") (pin "31") (pinfunction "VCC_31") (pintype "power_in"))
      (node (ref "IC22") (pin "35") (pinfunction "VCC_35") (pintype "power_in"))
      (node (ref "IC22") (pin "38") (pinfunction "VCC_38") (pintype "power_in"))
      (node (ref "IC22") (pin "42") (pinfunction "VCC_42") (pintype "power_in"))
      (node (ref "IC22") (pin "44") (pinfunction "BIASVCC_44") (pintype "input"))
      (node (ref "IC22") (pin "47") (pinfunction "VCC_47") (pintype "input"))
      (node (ref "IC22") (pin "7") (pinfunction "VCC_7") (pintype "power_in"))
      (node (ref "IC25") (pin "1") (pinfunction "~{1OEBY}_1") (pintype "input"))
      (node (ref "IC25") (pin "11") (pinfunction "LE_11") (pintype "input"))
      (node (ref "IC25") (pin "18") (pinfunction "VCC_18") (pintype "power_in"))
      (node (ref "IC25") (pin "25") (pinfunction "VCC_25") (pintype "power_in"))
      (node (ref "IC25") (pin "31") (pinfunction "VCC_31") (pintype "power_in"))
      (node (ref "IC25") (pin "35") (pinfunction "VCC_35") (pintype "power_in"))
      (node (ref "IC25") (pin "38") (pinfunction "VCC_38") (pintype "power_in"))
      (node (ref "IC25") (pin "42") (pinfunction "VCC_42") (pintype "power_in"))
      (node (ref "IC25") (pin "44") (pinfunction "BIASVCC_44") (pintype "input"))
      (node (ref "IC25") (pin "47") (pinfunction "VCC_47") (pintype "input"))
      (node (ref "IC25") (pin "7") (pinfunction "VCC_7") (pintype "power_in"))
      (node (ref "IC26") (pin "1") (pinfunction "~{1OEBY}_1") (pintype "input"))
      (node (ref "IC26") (pin "11") (pinfunction "LE_11") (pintype "input"))
      (node (ref "IC26") (pin "18") (pinfunction "VCC_18") (pintype "power_in"))
      (node (ref "IC26") (pin "25") (pinfunction "VCC_25") (pintype "power_in"))
      (node (ref "IC26") (pin "31") (pinfunction "VCC_31") (pintype "power_in"))
      (node (ref "IC26") (pin "35") (pinfunction "VCC_35") (pintype "power_in"))
      (node (ref "IC26") (pin "38") (pinfunction "VCC_38") (pintype "power_in"))
      (node (ref "IC26") (pin "42") (pinfunction "VCC_42") (pintype "power_in"))
      (node (ref "IC26") (pin "44") (pinfunction "BIASVCC_44") (pintype "input"))
      (node (ref "IC26") (pin "47") (pinfunction "VCC_47") (pintype "input"))
      (node (ref "IC26") (pin "7") (pinfunction "VCC_7") (pintype "power_in"))
      (node (ref "IC27") (pin "11") (pinfunction "LE_11") (pintype "input"))
      (node (ref "IC27") (pin "18") (pinfunction "VCC_18") (pintype "power_in"))
      (node (ref "IC27") (pin "25") (pinfunction "VCC_25") (pintype "power_in"))
      (node (ref "IC27") (pin "31") (pinfunction "VCC_31") (pintype "power_in"))
      (node (ref "IC27") (pin "35") (pinfunction "VCC_35") (pintype "power_in"))
      (node (ref "IC27") (pin "38") (pinfunction "VCC_38") (pintype "power_in"))
      (node (ref "IC27") (pin "42") (pinfunction "VCC_42") (pintype "power_in"))
      (node (ref "IC27") (pin "44") (pinfunction "BIASVCC_44") (pintype "input"))
      (node (ref "IC27") (pin "47") (pinfunction "VCC_47") (pintype "input"))
      (node (ref "IC27") (pin "7") (pinfunction "VCC_7") (pintype "power_in"))
      (node (ref "IC27") (pin "8") (pinfunction "2~{OEBY}_8") (pintype "input"))
      (node (ref "IC33") (pin "11") (pinfunction "LE_11") (pintype "input"))
      (node (ref "IC33") (pin "18") (pinfunction "VCC_18") (pintype "power_in"))
      (node (ref "IC33") (pin "25") (pinfunction "VCC_25") (pintype "power_in"))
      (node (ref "IC33") (pin "31") (pinfunction "VCC_31") (pintype "power_in"))
      (node (ref "IC33") (pin "35") (pinfunction "VCC_35") (pintype "power_in"))
      (node (ref "IC33") (pin "38") (pinfunction "VCC_38") (pintype "power_in"))
      (node (ref "IC33") (pin "41") (pinfunction "2OEAB_41") (pintype "input"))
      (node (ref "IC33") (pin "42") (pinfunction "VCC_42") (pintype "power_in"))
      (node (ref "IC33") (pin "44") (pinfunction "BIASVCC_44") (pintype "input"))
      (node (ref "IC33") (pin "47") (pinfunction "VCC_47") (pintype "input"))
      (node (ref "IC33") (pin "7") (pinfunction "VCC_7") (pintype "power_in"))
      (node (ref "IC33") (pin "8") (pinfunction "2~{OEBY}_8") (pintype "input"))
      (node (ref "IC35") (pin "1") (pinfunction "~{1OEBY}_1") (pintype "input"))
      (node (ref "IC35") (pin "11") (pinfunction "LE_11") (pintype "input"))
      (node (ref "IC35") (pin "18") (pinfunction "VCC_18") (pintype "power_in"))
      (node (ref "IC35") (pin "25") (pinfunction "VCC_25") (pintype "power_in"))
      (node (ref "IC35") (pin "31") (pinfunction "VCC_31") (pintype "power_in"))
      (node (ref "IC35") (pin "35") (pinfunction "VCC_35") (pintype "power_in"))
      (node (ref "IC35") (pin "38") (pinfunction "VCC_38") (pintype "power_in"))
      (node (ref "IC35") (pin "42") (pinfunction "VCC_42") (pintype "power_in"))
      (node (ref "IC35") (pin "44") (pinfunction "BIASVCC_44") (pintype "input"))
      (node (ref "IC35") (pin "47") (pinfunction "VCC_47") (pintype "input"))
      (node (ref "IC35") (pin "7") (pinfunction "VCC_7") (pintype "power_in"))
      (node (ref "IC35") (pin "8") (pinfunction "2~{OEBY}_8") (pintype "input"))
      (node (ref "IC42") (pin "1") (pinfunction "~{1OEBY}_1") (pintype "input"))
      (node (ref "IC42") (pin "11") (pinfunction "LE_11") (pintype "input"))
      (node (ref "IC42") (pin "18") (pinfunction "VCC_18") (pintype "power_in"))
      (node (ref "IC42") (pin "25") (pinfunction "VCC_25") (pintype "power_in"))
      (node (ref "IC42") (pin "31") (pinfunction "VCC_31") (pintype "power_in"))
      (node (ref "IC42") (pin "35") (pinfunction "VCC_35") (pintype "power_in"))
      (node (ref "IC42") (pin "38") (pinfunction "VCC_38") (pintype "power_in"))
      (node (ref "IC42") (pin "42") (pinfunction "VCC_42") (pintype "power_in"))
      (node (ref "IC42") (pin "44") (pinfunction "BIASVCC_44") (pintype "input"))
      (node (ref "IC42") (pin "47") (pinfunction "VCC_47") (pintype "input"))
      (node (ref "IC42") (pin "7") (pinfunction "VCC_7") (pintype "power_in"))
      (node (ref "IC42") (pin "8") (pinfunction "2~{OEBY}_8") (pintype "input"))
      (node (ref "IC5") (pin "1") (pinfunction "~{1OEBY}_1") (pintype "input"))
      (node (ref "IC5") (pin "11") (pinfunction "LE_11") (pintype "input"))
      (node (ref "IC5") (pin "18") (pinfunction "VCC_18") (pintype "power_in"))
      (node (ref "IC5") (pin "25") (pinfunction "VCC_25") (pintype "power_in"))
      (node (ref "IC5") (pin "31") (pinfunction "VCC_31") (pintype "power_in"))
      (node (ref "IC5") (pin "35") (pinfunction "VCC_35") (pintype "power_in"))
      (node (ref "IC5") (pin "38") (pinfunction "VCC_38") (pintype "power_in"))
      (node (ref "IC5") (pin "42") (pinfunction "VCC_42") (pintype "power_in"))
      (node (ref "IC5") (pin "44") (pinfunction "BIASVCC_44") (pintype "input"))
      (node (ref "IC5") (pin "47") (pinfunction "VCC_47") (pintype "input"))
      (node (ref "IC5") (pin "7") (pinfunction "VCC_7") (pintype "power_in"))
      (node (ref "IC5") (pin "8") (pinfunction "2~{OEBY}_8") (pintype "input"))
      (node (ref "P1") (pin "d12") (pinfunction "d12_d12") (pintype "bidirectional"))
      (node (ref "P1") (pin "d14") (pinfunction "d14_d14") (pintype "bidirectional"))
      (node (ref "P1") (pin "d16") (pinfunction "d16_d16") (pintype "bidirectional"))
      (node (ref "P1") (pin "d18") (pinfunction "d18_d18") (pintype "bidirectional"))
      (node (ref "P1") (pin "d20") (pinfunction "d20_d20") (pintype "bidirectional"))
      (node (ref "P1") (pin "d22") (pinfunction "d22_d22") (pintype "bidirectional"))
      (node (ref "P1") (pin "d24") (pinfunction "d24_d24") (pintype "bidirectional"))
      (node (ref "P1") (pin "d26") (pinfunction "d26_d26") (pintype "bidirectional"))
      (node (ref "P1") (pin "d28") (pinfunction "d28_d28") (pintype "bidirectional"))
      (node (ref "P1") (pin "d30") (pinfunction "d30_d30") (pintype "bidirectional"))
      (node (ref "R157") (pin "1") (pinfunction "1_1") (pintype "passive"))
      (node (ref "R158") (pin "1") (pinfunction "1_1") (pintype "passive"))
      (node (ref "R175") (pin "2") (pinfunction "2_2") (pintype "passive"))
      (node (ref "R203") (pin "2") (pinfunction "2_2") (pintype "passive"))
      (node (ref "R213") (pin "2") (pinfunction "2_2") (pintype "passive"))
      (node (ref "R216") (pin "2") (pinfunction "2_2") (pintype "passive"))
      (node (ref "R217") (pin "2") (pinfunction "2_2") (pintype "passive"))
      (node (ref "R223") (pin "2") (pinfunction "2_2") (pintype "passive"))
      (node (ref "R228") (pin "2") (pinfunction "2_2") (pintype "passive"))
      (node (ref "R230") (pin "2") (pinfunction "2_2") (pintype "passive"))
    )
    (net (code "276") (name "P5V_STDBY_VME") (class "Default")
      (node (ref "P1") (pin "b31") (pinfunction "b31_b31") (pintype "bidirectional"))
    )
    (net (code "277") (name "P5V_VME") (class "Default")
      (node (ref "P1") (pin "a32") (pinfunction "a32_a32") (pintype "bidirectional"))
      (node (ref "P1") (pin "b32") (pinfunction "b32_b32") (pintype "bidirectional"))
      (node (ref "P1") (pin "c32") (pinfunction "c32_c32") (pintype "bidirectional"))
      (node (ref "P3") (pin "b1") (pinfunction "b1_b1") (pintype "bidirectional"))
      (node (ref "P3") (pin "b13") (pinfunction "b13_b13") (pintype "bidirectional"))
      (node (ref "P3") (pin "b32") (pinfunction "b32_b32") (pintype "bidirectional"))
    )
    (net (code "278") (name "P12V_VME") (class "Default")
      (node (ref "P1") (pin "c31") (pinfunction "c31_c31") (pintype "bidirectional"))
    )
    (net (code "279") (name "unconnected-(IC5-1Y-Pad3)") (class "Default")
      (node (ref "IC5") (pin "3") (pinfunction "1Y_3") (pintype "output+no_connect"))
    )
    (net (code "280") (name "unconnected-(IC5-2Y-Pad6)") (class "Default")
      (node (ref "IC5") (pin "6") (pinfunction "2Y_6") (pintype "output+no_connect"))
    )
    (net (code "281") (name "unconnected-(IC15-1Y-Pad3)") (class "Default")
      (node (ref "IC15") (pin "3") (pinfunction "1Y_3") (pintype "output+no_connect"))
    )
    (net (code "282") (name "unconnected-(IC15-2Y-Pad6)") (class "Default")
      (node (ref "IC15") (pin "6") (pinfunction "2Y_6") (pintype "output+no_connect"))
    )
    (net (code "283") (name "unconnected-(IC25-1Y-Pad3)") (class "Default")
      (node (ref "IC25") (pin "3") (pinfunction "1Y_3") (pintype "output+no_connect"))
    )
    (net (code "284") (name "unconnected-(IC26-1Y-Pad3)") (class "Default")
      (node (ref "IC26") (pin "3") (pinfunction "1Y_3") (pintype "output+no_connect"))
    )
    (net (code "285") (name "unconnected-(IC27-2Y-Pad6)") (class "Default")
      (node (ref "IC27") (pin "6") (pinfunction "2Y_6") (pintype "output+no_connect"))
    )
    (net (code "286") (name "unconnected-(IC33-2Y-Pad6)") (class "Default")
      (node (ref "IC33") (pin "6") (pinfunction "2Y_6") (pintype "output+no_connect"))
    )
    (net (code "287") (name "unconnected-(IC35-1Y-Pad3)") (class "Default")
      (node (ref "IC35") (pin "3") (pinfunction "1Y_3") (pintype "output+no_connect"))
    )
    (net (code "288") (name "unconnected-(IC35-2Y-Pad6)") (class "Default")
      (node (ref "IC35") (pin "6") (pinfunction "2Y_6") (pintype "output+no_connect"))
    )
    (net (code "289") (name "unconnected-(IC42-1Y-Pad3)") (class "Default")
      (node (ref "IC42") (pin "3") (pinfunction "1Y_3") (pintype "output+no_connect"))
    )
    (net (code "290") (name "unconnected-(IC42-2Y-Pad6)") (class "Default")
      (node (ref "IC42") (pin "6") (pinfunction "2Y_6") (pintype "output+no_connect"))
    )
    (net (code "291") (name "unconnected-(P1-Padd1)") (class "Default")
      (node (ref "P1") (pin "d1") (pinfunction "d1_d1") (pintype "bidirectional+no_connect"))
    )
    (net (code "292") (name "unconnected-(P1-Padd3)") (class "Default")
      (node (ref "P1") (pin "d3") (pinfunction "d3_d3") (pintype "bidirectional+no_connect"))
    )
    (net (code "293") (name "unconnected-(P1-Padd4)") (class "Default")
      (node (ref "P1") (pin "d4") (pinfunction "d4_d4") (pintype "bidirectional+no_connect"))
    )
    (net (code "294") (name "unconnected-(P1-Padd5)") (class "Default")
      (node (ref "P1") (pin "d5") (pinfunction "d5_d5") (pintype "bidirectional+no_connect"))
    )
    (net (code "295") (name "unconnected-(P1-Padd6)") (class "Default")
      (node (ref "P1") (pin "d6") (pinfunction "d6_d6") (pintype "bidirectional+no_connect"))
    )
    (net (code "296") (name "unconnected-(P1-Padd7)") (class "Default")
      (node (ref "P1") (pin "d7") (pinfunction "d7_d7") (pintype "bidirectional+no_connect"))
    )
    (net (code "297") (name "unconnected-(P1-Padd8)") (class "Default")
      (node (ref "P1") (pin "d8") (pinfunction "d8_d8") (pintype "bidirectional+no_connect"))
    )
    (net (code "298") (name "unconnected-(P1-Padd19)") (class "Default")
      (node (ref "P1") (pin "d19") (pinfunction "d19_d19") (pintype "bidirectional+no_connect"))
    )
    (net (code "299") (name "unconnected-(P1-Padd21)") (class "Default")
      (node (ref "P1") (pin "d21") (pinfunction "d21_d21") (pintype "bidirectional+no_connect"))
    )
    (net (code "300") (name "unconnected-(P1-Padd23)") (class "Default")
      (node (ref "P1") (pin "d23") (pinfunction "d23_d23") (pintype "bidirectional+no_connect"))
    )
    (net (code "301") (name "unconnected-(P1-Padd25)") (class "Default")
      (node (ref "P1") (pin "d25") (pinfunction "d25_d25") (pintype "bidirectional+no_connect"))
    )
    (net (code "302") (name "unconnected-(P1-Padd27)") (class "Default")
      (node (ref "P1") (pin "d27") (pinfunction "d27_d27") (pintype "bidirectional+no_connect"))
    )
    (net (code "303") (name "unconnected-(P1-Padd29)") (class "Default")
      (node (ref "P1") (pin "d29") (pinfunction "d29_d29") (pintype "bidirectional+no_connect"))
    )
    (net (code "304") (name "unconnected-(P1-Padd32)") (class "Default")
      (node (ref "P1") (pin "d32") (pinfunction "d32_d32") (pintype "bidirectional+no_connect"))
    )
    (net (code "305") (name "unconnected-(P1-Padz11)") (class "Default")
      (node (ref "P1") (pin "z11") (pinfunction "z11_z11") (pintype "bidirectional+no_connect"))
    )
    (net (code "306") (name "unconnected-(P1-Padz13)") (class "Default")
      (node (ref "P1") (pin "z13") (pinfunction "z13_z13") (pintype "bidirectional+no_connect"))
    )
    (net (code "307") (name "unconnected-(P1-Padz15)") (class "Default")
      (node (ref "P1") (pin "z15") (pinfunction "z15_z15") (pintype "bidirectional+no_connect"))
    )
    (net (code "308") (name "unconnected-(P1-Padz17)") (class "Default")
      (node (ref "P1") (pin "z17") (pinfunction "z17_z17") (pintype "bidirectional+no_connect"))
    )
    (net (code "309") (name "unconnected-(P1-Padz19)") (class "Default")
      (node (ref "P1") (pin "z19") (pinfunction "z19_z19") (pintype "bidirectional+no_connect"))
    )
    (net (code "310") (name "unconnected-(P1-Padz21)") (class "Default")
      (node (ref "P1") (pin "z21") (pinfunction "z21_z21") (pintype "bidirectional+no_connect"))
    )
    (net (code "311") (name "unconnected-(P1-Padz23)") (class "Default")
      (node (ref "P1") (pin "z23") (pinfunction "z23_z23") (pintype "bidirectional+no_connect"))
    )
    (net (code "312") (name "unconnected-(P1-Padz25)") (class "Default")
      (node (ref "P1") (pin "z25") (pinfunction "z25_z25") (pintype "bidirectional+no_connect"))
    )
    (net (code "313") (name "unconnected-(P1-Padz27)") (class "Default")
      (node (ref "P1") (pin "z27") (pinfunction "z27_z27") (pintype "bidirectional+no_connect"))
    )
    (net (code "314") (name "unconnected-(P1-Padz29)") (class "Default")
      (node (ref "P1") (pin "z29") (pinfunction "z29_z29") (pintype "bidirectional+no_connect"))
    )
    (net (code "315") (name "unconnected-(P1-Padz31)") (class "Default")
      (node (ref "P1") (pin "z31") (pinfunction "z31_z31") (pintype "bidirectional+no_connect"))
    )
    (net (code "316") (name "unconnected-(P3-Padc1)") (class "Default")
      (node (ref "P3") (pin "c1") (pinfunction "c1_c1") (pintype "bidirectional"))
    )
    (net (code "317") (name "unconnected-(P3-Padc2)") (class "Default")
      (node (ref "P3") (pin "c2") (pinfunction "c2_c2") (pintype "bidirectional"))
    )
    (net (code "318") (name "unconnected-(P3-Padc3)") (class "Default")
      (node (ref "P3") (pin "c3") (pinfunction "c3_c3") (pintype "bidirectional"))
    )
    (net (code "319") (name "unconnected-(P3-Padc4)") (class "Default")
      (node (ref "P3") (pin "c4") (pinfunction "c4_c4") (pintype "bidirectional"))
    )
    (net (code "320") (name "unconnected-(P3-Padc5)") (class "Default")
      (node (ref "P3") (pin "c5") (pinfunction "c5_c5") (pintype "bidirectional"))
    )
    (net (code "321") (name "unconnected-(P3-Padc6)") (class "Default")
      (node (ref "P3") (pin "c6") (pinfunction "c6_c6") (pintype "bidirectional"))
    )
    (net (code "322") (name "unconnected-(P3-Padc7)") (class "Default")
      (node (ref "P3") (pin "c7") (pinfunction "c7_c7") (pintype "bidirectional"))
    )
    (net (code "323") (name "unconnected-(P3-Padc8)") (class "Default")
      (node (ref "P3") (pin "c8") (pinfunction "c8_c8") (pintype "bidirectional"))
    )
    (net (code "324") (name "unconnected-(P3-Padc9)") (class "Default")
      (node (ref "P3") (pin "c9") (pinfunction "c9_c9") (pintype "bidirectional"))
    )
    (net (code "325") (name "unconnected-(P3-Padc10)") (class "Default")
      (node (ref "P3") (pin "c10") (pinfunction "c10_c10") (pintype "bidirectional"))
    )
    (net (code "326") (name "unconnected-(P3-Padc11)") (class "Default")
      (node (ref "P3") (pin "c11") (pinfunction "c11_c11") (pintype "bidirectional"))
    )
    (net (code "327") (name "unconnected-(P3-Padc12)") (class "Default")
      (node (ref "P3") (pin "c12") (pinfunction "c12_c12") (pintype "bidirectional"))
    )
    (net (code "328") (name "unconnected-(P3-Padc13)") (class "Default")
      (node (ref "P3") (pin "c13") (pinfunction "c13_c13") (pintype "bidirectional"))
    )
    (net (code "329") (name "unconnected-(P3-Padc14)") (class "Default")
      (node (ref "P3") (pin "c14") (pinfunction "c14_c14") (pintype "bidirectional"))
    )
    (net (code "330") (name "unconnected-(P3-Padc15)") (class "Default")
      (node (ref "P3") (pin "c15") (pinfunction "c15_c15") (pintype "bidirectional"))
    )
    (net (code "331") (name "unconnected-(P3-Padc16)") (class "Default")
      (node (ref "P3") (pin "c16") (pinfunction "c16_c16") (pintype "bidirectional"))
    )
    (net (code "332") (name "unconnected-(P3-Padc17)") (class "Default")
      (node (ref "P3") (pin "c17") (pinfunction "c17_c17") (pintype "bidirectional"))
    )
    (net (code "333") (name "unconnected-(P3-Padc18)") (class "Default")
      (node (ref "P3") (pin "c18") (pinfunction "c18_c18") (pintype "bidirectional"))
    )
    (net (code "334") (name "unconnected-(P3-Padc19)") (class "Default")
      (node (ref "P3") (pin "c19") (pinfunction "c19_c19") (pintype "bidirectional"))
    )
    (net (code "335") (name "unconnected-(P3-Padc20)") (class "Default")
      (node (ref "P3") (pin "c20") (pinfunction "c20_c20") (pintype "bidirectional"))
    )
    (net (code "336") (name "unconnected-(P3-Padc21)") (class "Default")
      (node (ref "P3") (pin "c21") (pinfunction "c21_c21") (pintype "bidirectional"))
    )
    (net (code "337") (name "unconnected-(P3-Padc22)") (class "Default")
      (node (ref "P3") (pin "c22") (pinfunction "c22_c22") (pintype "bidirectional"))
    )
    (net (code "338") (name "unconnected-(P3-Padd32)") (class "Default")
      (node (ref "P3") (pin "d32") (pinfunction "d32_d32") (pintype "bidirectional+no_connect"))
    )
    (net (code "339") (name "unconnected-(P3-Padz1)") (class "Default")
      (node (ref "P3") (pin "z1") (pinfunction "z1_z1") (pintype "bidirectional+no_connect"))
    )
    (net (code "340") (name "unconnected-(P3-Padz3)") (class "Default")
      (node (ref "P3") (pin "z3") (pinfunction "z3_z3") (pintype "bidirectional+no_connect"))
    )
    (net (code "341") (name "unconnected-(P3-Padz5)") (class "Default")
      (node (ref "P3") (pin "z5") (pinfunction "z5_z5") (pintype "bidirectional+no_connect"))
    )
    (net (code "342") (name "unconnected-(P3-Padz7)") (class "Default")
      (node (ref "P3") (pin "z7") (pinfunction "z7_z7") (pintype "bidirectional+no_connect"))
    )
    (net (code "343") (name "unconnected-(P3-Padz9)") (class "Default")
      (node (ref "P3") (pin "z9") (pinfunction "z9_z9") (pintype "bidirectional+no_connect"))
    )
    (net (code "344") (name "unconnected-(P3-Padz11)") (class "Default")
      (node (ref "P3") (pin "z11") (pinfunction "z11_z11") (pintype "bidirectional+no_connect"))
    )
    (net (code "345") (name "unconnected-(P3-Padz13)") (class "Default")
      (node (ref "P3") (pin "z13") (pinfunction "z13_z13") (pintype "bidirectional+no_connect"))
    )
    (net (code "346") (name "unconnected-(P3-Padz15)") (class "Default")
      (node (ref "P3") (pin "z15") (pinfunction "z15_z15") (pintype "bidirectional+no_connect"))
    )
    (net (code "347") (name "unconnected-(P3-Padz17)") (class "Default")
      (node (ref "P3") (pin "z17") (pinfunction "z17_z17") (pintype "bidirectional+no_connect"))
    )
    (net (code "348") (name "unconnected-(P3-Padz19)") (class "Default")
      (node (ref "P3") (pin "z19") (pinfunction "z19_z19") (pintype "bidirectional+no_connect"))
    )
    (net (code "349") (name "unconnected-(P3-Padz21)") (class "Default")
      (node (ref "P3") (pin "z21") (pinfunction "z21_z21") (pintype "bidirectional+no_connect"))
    )
    (net (code "350") (name "unconnected-(P3-Padz23)") (class "Default")
      (node (ref "P3") (pin "z23") (pinfunction "z23_z23") (pintype "bidirectional+no_connect"))
    )
    (net (code "351") (name "unconnected-(P3-Padz25)") (class "Default")
      (node (ref "P3") (pin "z25") (pinfunction "z25_z25") (pintype "bidirectional+no_connect"))
    )
    (net (code "352") (name "unconnected-(P3-Padz27)") (class "Default")
      (node (ref "P3") (pin "z27") (pinfunction "z27_z27") (pintype "bidirectional+no_connect"))
    )
    (net (code "353") (name "unconnected-(P3-Padz29)") (class "Default")
      (node (ref "P3") (pin "z29") (pinfunction "z29_z29") (pintype "bidirectional+no_connect"))
    )
    (net (code "354") (name "unconnected-(P3-Padz31)") (class "Default")
      (node (ref "P3") (pin "z31") (pinfunction "z31_z31") (pintype "bidirectional+no_connect"))
    )
  )
)
